# ina219.net
KiCad netlist of a schematic drawn in Altium Designer
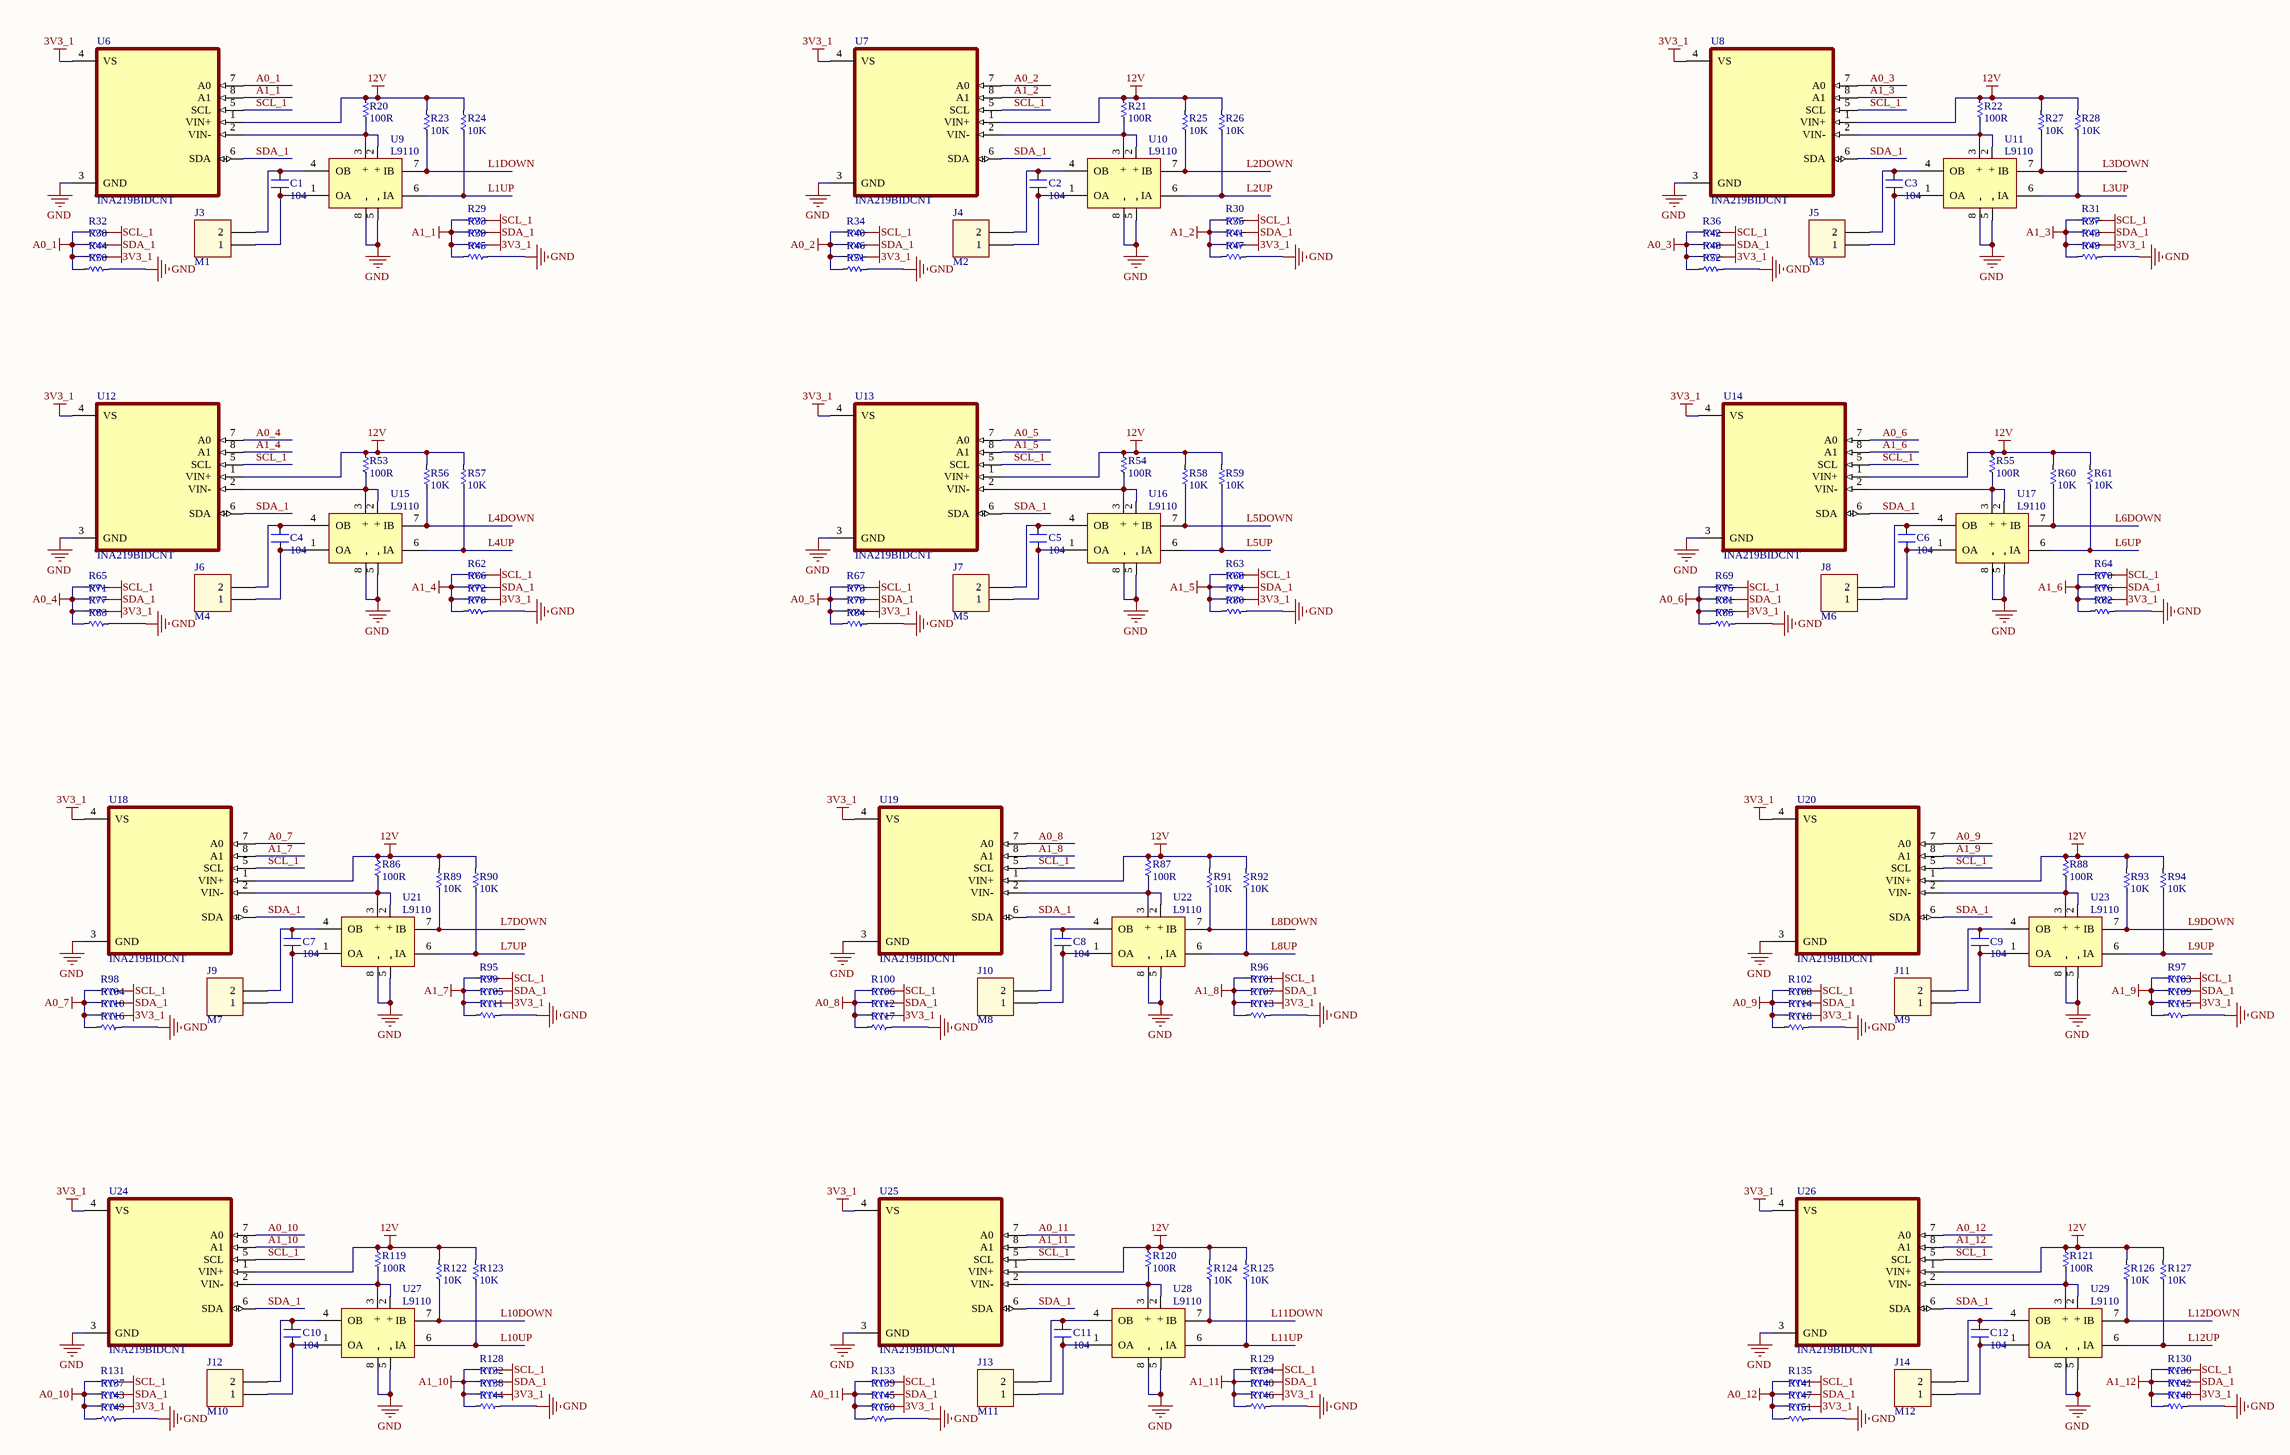
[diagram p0: ina219.SchDoc]

(export (version "E")
  (design (tool "Eeschema 10.0.6"))
  (components
    (comp (ref "C1")
      (value "104")
      (footprint "SM-CAP-0805")
      (fields (field (name "DESIGNED BY") "VanDungEvn"))
      (libsource (lib "electronicvn-library1") (part "CN"))
    )
    (comp (ref "C2")
      (value "104")
      (footprint "SM-CAP-0805")
      (fields (field (name "DESIGNED BY") "VanDungEvn"))
      (libsource (lib "electronicvn-library1") (part "CN"))
    )
    (comp (ref "C3")
      (value "104")
      (footprint "SM-CAP-0805")
      (fields (field (name "DESIGNED BY") "VanDungEvn"))
      (libsource (lib "electronicvn-library1") (part "CN"))
    )
    (comp (ref "C4")
      (value "104")
      (footprint "SM-CAP-0805")
      (fields (field (name "DESIGNED BY") "VanDungEvn"))
      (libsource (lib "electronicvn-library1") (part "CN"))
    )
    (comp (ref "C5")
      (value "104")
      (footprint "SM-CAP-0805")
      (fields (field (name "DESIGNED BY") "VanDungEvn"))
      (libsource (lib "electronicvn-library1") (part "CN"))
    )
    (comp (ref "C6")
      (value "104")
      (footprint "SM-CAP-0805")
      (fields (field (name "DESIGNED BY") "VanDungEvn"))
      (libsource (lib "electronicvn-library1") (part "CN"))
    )
    (comp (ref "C7")
      (value "104")
      (footprint "SM-CAP-0805")
      (fields (field (name "DESIGNED BY") "VanDungEvn"))
      (libsource (lib "electronicvn-library1") (part "CN"))
    )
    (comp (ref "C8")
      (value "104")
      (footprint "SM-CAP-0805")
      (fields (field (name "DESIGNED BY") "VanDungEvn"))
      (libsource (lib "electronicvn-library1") (part "CN"))
    )
    (comp (ref "C9")
      (value "104")
      (footprint "SM-CAP-0805")
      (fields (field (name "DESIGNED BY") "VanDungEvn"))
      (libsource (lib "electronicvn-library1") (part "CN"))
    )
    (comp (ref "C10")
      (value "104")
      (footprint "SM-CAP-0805")
      (fields (field (name "DESIGNED BY") "VanDungEvn"))
      (libsource (lib "electronicvn-library1") (part "CN"))
    )
    (comp (ref "C11")
      (value "104")
      (footprint "SM-CAP-0805")
      (fields (field (name "DESIGNED BY") "VanDungEvn"))
      (libsource (lib "electronicvn-library1") (part "CN"))
    )
    (comp (ref "C12")
      (value "104")
      (footprint "SM-CAP-0805")
      (fields (field (name "DESIGNED BY") "VanDungEvn"))
      (libsource (lib "electronicvn-library1") (part "CN"))
    )
    (comp (ref "J3")
      (value "M1")
      (footprint "62000211622")
      (description "WR-WTB 2.00mm Male Vertical Shrouded Header, 2p")
      (fields (field (name "PART NUMBER") "62000211622") (field (name "PUBLISHER") "Wurth Elektronik"))
      (libsource (lib "Header2.0") (part "62000211622"))
    )
    (comp (ref "J4")
      (value "M2")
      (footprint "62000211622")
      (description "WR-WTB 2.00mm Male Vertical Shrouded Header, 2p")
      (fields (field (name "PART NUMBER") "62000211622") (field (name "PUBLISHER") "Wurth Elektronik"))
      (libsource (lib "Header2.0") (part "62000211622"))
    )
    (comp (ref "J5")
      (value "M3")
      (footprint "62000211622")
      (description "WR-WTB 2.00mm Male Vertical Shrouded Header, 2p")
      (fields (field (name "PART NUMBER") "62000211622") (field (name "PUBLISHER") "Wurth Elektronik"))
      (libsource (lib "Header2.0") (part "62000211622"))
    )
    (comp (ref "J6")
      (value "M4")
      (footprint "62000211622")
      (description "WR-WTB 2.00mm Male Vertical Shrouded Header, 2p")
      (fields (field (name "PART NUMBER") "62000211622") (field (name "PUBLISHER") "Wurth Elektronik"))
      (libsource (lib "Header2.0") (part "62000211622"))
    )
    (comp (ref "J7")
      (value "M5")
      (footprint "62000211622")
      (description "WR-WTB 2.00mm Male Vertical Shrouded Header, 2p")
      (fields (field (name "PART NUMBER") "62000211622") (field (name "PUBLISHER") "Wurth Elektronik"))
      (libsource (lib "Header2.0") (part "62000211622"))
    )
    (comp (ref "J8")
      (value "M6")
      (footprint "62000211622")
      (description "WR-WTB 2.00mm Male Vertical Shrouded Header, 2p")
      (fields (field (name "PART NUMBER") "62000211622") (field (name "PUBLISHER") "Wurth Elektronik"))
      (libsource (lib "Header2.0") (part "62000211622"))
    )
    (comp (ref "J9")
      (value "M7")
      (footprint "62000211622")
      (description "WR-WTB 2.00mm Male Vertical Shrouded Header, 2p")
      (fields (field (name "PART NUMBER") "62000211622") (field (name "PUBLISHER") "Wurth Elektronik"))
      (libsource (lib "Header2.0") (part "62000211622"))
    )
    (comp (ref "J10")
      (value "M8")
      (footprint "62000211622")
      (description "WR-WTB 2.00mm Male Vertical Shrouded Header, 2p")
      (fields (field (name "PART NUMBER") "62000211622") (field (name "PUBLISHER") "Wurth Elektronik"))
      (libsource (lib "Header2.0") (part "62000211622"))
    )
    (comp (ref "J11")
      (value "M9")
      (footprint "62000211622")
      (description "WR-WTB 2.00mm Male Vertical Shrouded Header, 2p")
      (fields (field (name "PART NUMBER") "62000211622") (field (name "PUBLISHER") "Wurth Elektronik"))
      (libsource (lib "Header2.0") (part "62000211622"))
    )
    (comp (ref "J12")
      (value "M10")
      (footprint "62000211622")
      (description "WR-WTB 2.00mm Male Vertical Shrouded Header, 2p")
      (fields (field (name "PART NUMBER") "62000211622") (field (name "PUBLISHER") "Wurth Elektronik"))
      (libsource (lib "Header2.0") (part "62000211622"))
    )
    (comp (ref "J13")
      (value "M11")
      (footprint "62000211622")
      (description "WR-WTB 2.00mm Male Vertical Shrouded Header, 2p")
      (fields (field (name "PART NUMBER") "62000211622") (field (name "PUBLISHER") "Wurth Elektronik"))
      (libsource (lib "Header2.0") (part "62000211622"))
    )
    (comp (ref "J14")
      (value "M12")
      (footprint "62000211622")
      (description "WR-WTB 2.00mm Male Vertical Shrouded Header, 2p")
      (fields (field (name "PART NUMBER") "62000211622") (field (name "PUBLISHER") "Wurth Elektronik"))
      (libsource (lib "Header2.0") (part "62000211622"))
    )
    (comp (ref "R20")
      (value "100R")
      (footprint "RES-SMD-2512")
      (description "Resistor")
      (fields
        (field (name "MANUFACTURER") "Generic Components")
        (field (name "PUBLISHER") "Altium Hobart Technology Centre")
      )
      (libsource (lib "LIBRARY") (part "Res-SMD"))
    )
    (comp (ref "R21")
      (value "100R")
      (footprint "RES-SMD-2512")
      (description "Resistor")
      (fields
        (field (name "MANUFACTURER") "Generic Components")
        (field (name "PUBLISHER") "Altium Hobart Technology Centre")
      )
      (libsource (lib "LIBRARY") (part "Res-SMD"))
    )
    (comp (ref "R22")
      (value "100R")
      (footprint "RES-SMD-2512")
      (description "Resistor")
      (fields
        (field (name "MANUFACTURER") "Generic Components")
        (field (name "PUBLISHER") "Altium Hobart Technology Centre")
      )
      (libsource (lib "LIBRARY") (part "Res-SMD"))
    )
    (comp (ref "R23")
      (value "10K")
      (footprint "RES-SMD-0805")
      (description "Resistor")
      (fields
        (field (name "MANUFACTURER") "Generic Components")
        (field (name "PUBLISHER") "Altium Hobart Technology Centre")
      )
      (libsource (lib "LIBRARY") (part "Res-SMD"))
    )
    (comp (ref "R24")
      (value "10K")
      (footprint "RES-SMD-0805")
      (description "Resistor")
      (fields
        (field (name "MANUFACTURER") "Generic Components")
        (field (name "PUBLISHER") "Altium Hobart Technology Centre")
      )
      (libsource (lib "LIBRARY") (part "Res-SMD"))
    )
    (comp (ref "R25")
      (value "10K")
      (footprint "RES-SMD-0805")
      (description "Resistor")
      (fields
        (field (name "MANUFACTURER") "Generic Components")
        (field (name "PUBLISHER") "Altium Hobart Technology Centre")
      )
      (libsource (lib "LIBRARY") (part "Res-SMD"))
    )
    (comp (ref "R26")
      (value "10K")
      (footprint "RES-SMD-0805")
      (description "Resistor")
      (fields
        (field (name "MANUFACTURER") "Generic Components")
        (field (name "PUBLISHER") "Altium Hobart Technology Centre")
      )
      (libsource (lib "LIBRARY") (part "Res-SMD"))
    )
    (comp (ref "R27")
      (value "10K")
      (footprint "RES-SMD-0805")
      (description "Resistor")
      (fields
        (field (name "MANUFACTURER") "Generic Components")
        (field (name "PUBLISHER") "Altium Hobart Technology Centre")
      )
      (libsource (lib "LIBRARY") (part "Res-SMD"))
    )
    (comp (ref "R28")
      (value "10K")
      (footprint "RES-SMD-0805")
      (description "Resistor")
      (fields
        (field (name "MANUFACTURER") "Generic Components")
        (field (name "PUBLISHER") "Altium Hobart Technology Centre")
      )
      (libsource (lib "LIBRARY") (part "Res-SMD"))
    )
    (comp (ref "R29")
      (value "Res")
      (footprint "RES-SMD-0603")
      (description "Resistor")
      (fields
        (field (name "MANUFACTURER") "Generic Components")
        (field (name "PUBLISHER") "Altium Hobart Technology Centre")
      )
      (libsource (lib "LIBRARY") (part "Res-SMD"))
    )
    (comp (ref "R30")
      (value "Res")
      (footprint "RES-SMD-0603")
      (description "Resistor")
      (fields
        (field (name "MANUFACTURER") "Generic Components")
        (field (name "PUBLISHER") "Altium Hobart Technology Centre")
      )
      (libsource (lib "LIBRARY") (part "Res-SMD"))
    )
    (comp (ref "R31")
      (value "Res")
      (footprint "RES-SMD-0603")
      (description "Resistor")
      (fields
        (field (name "MANUFACTURER") "Generic Components")
        (field (name "PUBLISHER") "Altium Hobart Technology Centre")
      )
      (libsource (lib "LIBRARY") (part "Res-SMD"))
    )
    (comp (ref "R32")
      (value "Res")
      (footprint "RES-SMD-0603")
      (description "Resistor")
      (fields
        (field (name "MANUFACTURER") "Generic Components")
        (field (name "PUBLISHER") "Altium Hobart Technology Centre")
      )
      (libsource (lib "LIBRARY") (part "Res-SMD"))
    )
    (comp (ref "R33")
      (value "Res")
      (footprint "RES-SMD-0603")
      (description "Resistor")
      (fields
        (field (name "MANUFACTURER") "Generic Components")
        (field (name "PUBLISHER") "Altium Hobart Technology Centre")
      )
      (libsource (lib "LIBRARY") (part "Res-SMD"))
    )
    (comp (ref "R34")
      (value "Res")
      (footprint "RES-SMD-0603")
      (description "Resistor")
      (fields
        (field (name "MANUFACTURER") "Generic Components")
        (field (name "PUBLISHER") "Altium Hobart Technology Centre")
      )
      (libsource (lib "LIBRARY") (part "Res-SMD"))
    )
    (comp (ref "R35")
      (value "Res")
      (footprint "RES-SMD-0603")
      (description "Resistor")
      (fields
        (field (name "MANUFACTURER") "Generic Components")
        (field (name "PUBLISHER") "Altium Hobart Technology Centre")
      )
      (libsource (lib "LIBRARY") (part "Res-SMD"))
    )
    (comp (ref "R36")
      (value "Res")
      (footprint "RES-SMD-0603")
      (description "Resistor")
      (fields
        (field (name "MANUFACTURER") "Generic Components")
        (field (name "PUBLISHER") "Altium Hobart Technology Centre")
      )
      (libsource (lib "LIBRARY") (part "Res-SMD"))
    )
    (comp (ref "R37")
      (value "Res")
      (footprint "RES-SMD-0603")
      (description "Resistor")
      (fields
        (field (name "MANUFACTURER") "Generic Components")
        (field (name "PUBLISHER") "Altium Hobart Technology Centre")
      )
      (libsource (lib "LIBRARY") (part "Res-SMD"))
    )
    (comp (ref "R38")
      (value "Res")
      (footprint "RES-SMD-0603")
      (description "Resistor")
      (fields
        (field (name "MANUFACTURER") "Generic Components")
        (field (name "PUBLISHER") "Altium Hobart Technology Centre")
      )
      (libsource (lib "LIBRARY") (part "Res-SMD"))
    )
    (comp (ref "R39")
      (value "Res")
      (footprint "RES-SMD-0603")
      (description "Resistor")
      (fields
        (field (name "MANUFACTURER") "Generic Components")
        (field (name "PUBLISHER") "Altium Hobart Technology Centre")
      )
      (libsource (lib "LIBRARY") (part "Res-SMD"))
    )
    (comp (ref "R40")
      (value "Res")
      (footprint "RES-SMD-0603")
      (description "Resistor")
      (fields
        (field (name "MANUFACTURER") "Generic Components")
        (field (name "PUBLISHER") "Altium Hobart Technology Centre")
      )
      (libsource (lib "LIBRARY") (part "Res-SMD"))
    )
    (comp (ref "R41")
      (value "Res")
      (footprint "RES-SMD-0603")
      (description "Resistor")
      (fields
        (field (name "MANUFACTURER") "Generic Components")
        (field (name "PUBLISHER") "Altium Hobart Technology Centre")
      )
      (libsource (lib "LIBRARY") (part "Res-SMD"))
    )
    (comp (ref "R42")
      (value "Res")
      (footprint "RES-SMD-0603")
      (description "Resistor")
      (fields
        (field (name "MANUFACTURER") "Generic Components")
        (field (name "PUBLISHER") "Altium Hobart Technology Centre")
      )
      (libsource (lib "LIBRARY") (part "Res-SMD"))
    )
    (comp (ref "R43")
      (value "Res")
      (footprint "RES-SMD-0603")
      (description "Resistor")
      (fields
        (field (name "MANUFACTURER") "Generic Components")
        (field (name "PUBLISHER") "Altium Hobart Technology Centre")
      )
      (libsource (lib "LIBRARY") (part "Res-SMD"))
    )
    (comp (ref "R44")
      (value "Res")
      (footprint "RES-SMD-0603")
      (description "Resistor")
      (fields
        (field (name "MANUFACTURER") "Generic Components")
        (field (name "PUBLISHER") "Altium Hobart Technology Centre")
      )
      (libsource (lib "LIBRARY") (part "Res-SMD"))
    )
    (comp (ref "R45")
      (value "Res")
      (footprint "RES-SMD-0603")
      (description "Resistor")
      (fields
        (field (name "MANUFACTURER") "Generic Components")
        (field (name "PUBLISHER") "Altium Hobart Technology Centre")
      )
      (libsource (lib "LIBRARY") (part "Res-SMD"))
    )
    (comp (ref "R46")
      (value "Res")
      (footprint "RES-SMD-0603")
      (description "Resistor")
      (fields
        (field (name "MANUFACTURER") "Generic Components")
        (field (name "PUBLISHER") "Altium Hobart Technology Centre")
      )
      (libsource (lib "LIBRARY") (part "Res-SMD"))
    )
    (comp (ref "R47")
      (value "Res")
      (footprint "RES-SMD-0603")
      (description "Resistor")
      (fields
        (field (name "MANUFACTURER") "Generic Components")
        (field (name "PUBLISHER") "Altium Hobart Technology Centre")
      )
      (libsource (lib "LIBRARY") (part "Res-SMD"))
    )
    (comp (ref "R48")
      (value "Res")
      (footprint "RES-SMD-0603")
      (description "Resistor")
      (fields
        (field (name "MANUFACTURER") "Generic Components")
        (field (name "PUBLISHER") "Altium Hobart Technology Centre")
      )
      (libsource (lib "LIBRARY") (part "Res-SMD"))
    )
    (comp (ref "R49")
      (value "Res")
      (footprint "RES-SMD-0603")
      (description "Resistor")
      (fields
        (field (name "MANUFACTURER") "Generic Components")
        (field (name "PUBLISHER") "Altium Hobart Technology Centre")
      )
      (libsource (lib "LIBRARY") (part "Res-SMD"))
    )
    (comp (ref "R50")
      (value "Res")
      (footprint "RES-SMD-0603")
      (description "Resistor")
      (fields
        (field (name "MANUFACTURER") "Generic Components")
        (field (name "PUBLISHER") "Altium Hobart Technology Centre")
      )
      (libsource (lib "LIBRARY") (part "Res-SMD"))
    )
    (comp (ref "R51")
      (value "Res")
      (footprint "RES-SMD-0603")
      (description "Resistor")
      (fields
        (field (name "MANUFACTURER") "Generic Components")
        (field (name "PUBLISHER") "Altium Hobart Technology Centre")
      )
      (libsource (lib "LIBRARY") (part "Res-SMD"))
    )
    (comp (ref "R52")
      (value "Res")
      (footprint "RES-SMD-0603")
      (description "Resistor")
      (fields
        (field (name "MANUFACTURER") "Generic Components")
        (field (name "PUBLISHER") "Altium Hobart Technology Centre")
      )
      (libsource (lib "LIBRARY") (part "Res-SMD"))
    )
    (comp (ref "R53")
      (value "100R")
      (footprint "RES-SMD-2512")
      (description "Resistor")
      (fields
        (field (name "MANUFACTURER") "Generic Components")
        (field (name "PUBLISHER") "Altium Hobart Technology Centre")
      )
      (libsource (lib "LIBRARY") (part "Res-SMD"))
    )
    (comp (ref "R54")
      (value "100R")
      (footprint "RES-SMD-2512")
      (description "Resistor")
      (fields
        (field (name "MANUFACTURER") "Generic Components")
        (field (name "PUBLISHER") "Altium Hobart Technology Centre")
      )
      (libsource (lib "LIBRARY") (part "Res-SMD"))
    )
    (comp (ref "R55")
      (value "100R")
      (footprint "RES-SMD-2512")
      (description "Resistor")
      (fields
        (field (name "MANUFACTURER") "Generic Components")
        (field (name "PUBLISHER") "Altium Hobart Technology Centre")
      )
      (libsource (lib "LIBRARY") (part "Res-SMD"))
    )
    (comp (ref "R56")
      (value "10K")
      (footprint "RES-SMD-0805")
      (description "Resistor")
      (fields
        (field (name "MANUFACTURER") "Generic Components")
        (field (name "PUBLISHER") "Altium Hobart Technology Centre")
      )
      (libsource (lib "LIBRARY") (part "Res-SMD"))
    )
    (comp (ref "R57")
      (value "10K")
      (footprint "RES-SMD-0805")
      (description "Resistor")
      (fields
        (field (name "MANUFACTURER") "Generic Components")
        (field (name "PUBLISHER") "Altium Hobart Technology Centre")
      )
      (libsource (lib "LIBRARY") (part "Res-SMD"))
    )
    (comp (ref "R58")
      (value "10K")
      (footprint "RES-SMD-0805")
      (description "Resistor")
      (fields
        (field (name "MANUFACTURER") "Generic Components")
        (field (name "PUBLISHER") "Altium Hobart Technology Centre")
      )
      (libsource (lib "LIBRARY") (part "Res-SMD"))
    )
    (comp (ref "R59")
      (value "10K")
      (footprint "RES-SMD-0805")
      (description "Resistor")
      (fields
        (field (name "MANUFACTURER") "Generic Components")
        (field (name "PUBLISHER") "Altium Hobart Technology Centre")
      )
      (libsource (lib "LIBRARY") (part "Res-SMD"))
    )
    (comp (ref "R60")
      (value "10K")
      (footprint "RES-SMD-0805")
      (description "Resistor")
      (fields
        (field (name "MANUFACTURER") "Generic Components")
        (field (name "PUBLISHER") "Altium Hobart Technology Centre")
      )
      (libsource (lib "LIBRARY") (part "Res-SMD"))
    )
    (comp (ref "R61")
      (value "10K")
      (footprint "RES-SMD-0805")
      (description "Resistor")
      (fields
        (field (name "MANUFACTURER") "Generic Components")
        (field (name "PUBLISHER") "Altium Hobart Technology Centre")
      )
      (libsource (lib "LIBRARY") (part "Res-SMD"))
    )
    (comp (ref "R62")
      (value "Res")
      (footprint "RES-SMD-0603")
      (description "Resistor")
      (fields
        (field (name "MANUFACTURER") "Generic Components")
        (field (name "PUBLISHER") "Altium Hobart Technology Centre")
      )
      (libsource (lib "LIBRARY") (part "Res-SMD"))
    )
    (comp (ref "R63")
      (value "Res")
      (footprint "RES-SMD-0603")
      (description "Resistor")
      (fields
        (field (name "MANUFACTURER") "Generic Components")
        (field (name "PUBLISHER") "Altium Hobart Technology Centre")
      )
      (libsource (lib "LIBRARY") (part "Res-SMD"))
    )
    (comp (ref "R64")
      (value "Res")
      (footprint "RES-SMD-0603")
      (description "Resistor")
      (fields
        (field (name "MANUFACTURER") "Generic Components")
        (field (name "PUBLISHER") "Altium Hobart Technology Centre")
      )
      (libsource (lib "LIBRARY") (part "Res-SMD"))
    )
    (comp (ref "R65")
      (value "Res")
      (footprint "RES-SMD-0603")
      (description "Resistor")
      (fields
        (field (name "MANUFACTURER") "Generic Components")
        (field (name "PUBLISHER") "Altium Hobart Technology Centre")
      )
      (libsource (lib "LIBRARY") (part "Res-SMD"))
    )
    (comp (ref "R66")
      (value "Res")
      (footprint "RES-SMD-0603")
      (description "Resistor")
      (fields
        (field (name "MANUFACTURER") "Generic Components")
        (field (name "PUBLISHER") "Altium Hobart Technology Centre")
      )
      (libsource (lib "LIBRARY") (part "Res-SMD"))
    )
    (comp (ref "R67")
      (value "Res")
      (footprint "RES-SMD-0603")
      (description "Resistor")
      (fields
        (field (name "MANUFACTURER") "Generic Components")
        (field (name "PUBLISHER") "Altium Hobart Technology Centre")
      )
      (libsource (lib "LIBRARY") (part "Res-SMD"))
    )
    (comp (ref "R68")
      (value "Res")
      (footprint "RES-SMD-0603")
      (description "Resistor")
      (fields
        (field (name "MANUFACTURER") "Generic Components")
        (field (name "PUBLISHER") "Altium Hobart Technology Centre")
      )
      (libsource (lib "LIBRARY") (part "Res-SMD"))
    )
    (comp (ref "R69")
      (value "Res")
      (footprint "RES-SMD-0603")
      (description "Resistor")
      (fields
        (field (name "MANUFACTURER") "Generic Components")
        (field (name "PUBLISHER") "Altium Hobart Technology Centre")
      )
      (libsource (lib "LIBRARY") (part "Res-SMD"))
    )
    (comp (ref "R70")
      (value "Res")
      (footprint "RES-SMD-0603")
      (description "Resistor")
      (fields
        (field (name "MANUFACTURER") "Generic Components")
        (field (name "PUBLISHER") "Altium Hobart Technology Centre")
      )
      (libsource (lib "LIBRARY") (part "Res-SMD"))
    )
    (comp (ref "R71")
      (value "Res")
      (footprint "RES-SMD-0603")
      (description "Resistor")
      (fields
        (field (name "MANUFACTURER") "Generic Components")
        (field (name "PUBLISHER") "Altium Hobart Technology Centre")
      )
      (libsource (lib "LIBRARY") (part "Res-SMD"))
    )
    (comp (ref "R72")
      (value "Res")
      (footprint "RES-SMD-0603")
      (description "Resistor")
      (fields
        (field (name "MANUFACTURER") "Generic Components")
        (field (name "PUBLISHER") "Altium Hobart Technology Centre")
      )
      (libsource (lib "LIBRARY") (part "Res-SMD"))
    )
    (comp (ref "R73")
      (value "Res")
      (footprint "RES-SMD-0603")
      (description "Resistor")
      (fields
        (field (name "MANUFACTURER") "Generic Components")
        (field (name "PUBLISHER") "Altium Hobart Technology Centre")
      )
      (libsource (lib "LIBRARY") (part "Res-SMD"))
    )
    (comp (ref "R74")
      (value "Res")
      (footprint "RES-SMD-0603")
      (description "Resistor")
      (fields
        (field (name "MANUFACTURER") "Generic Components")
        (field (name "PUBLISHER") "Altium Hobart Technology Centre")
      )
      (libsource (lib "LIBRARY") (part "Res-SMD"))
    )
    (comp (ref "R75")
      (value "Res")
      (footprint "RES-SMD-0603")
      (description "Resistor")
      (fields
        (field (name "MANUFACTURER") "Generic Components")
        (field (name "PUBLISHER") "Altium Hobart Technology Centre")
      )
      (libsource (lib "LIBRARY") (part "Res-SMD"))
    )
    (comp (ref "R76")
      (value "Res")
      (footprint "RES-SMD-0603")
      (description "Resistor")
      (fields
        (field (name "MANUFACTURER") "Generic Components")
        (field (name "PUBLISHER") "Altium Hobart Technology Centre")
      )
      (libsource (lib "LIBRARY") (part "Res-SMD"))
    )
    (comp (ref "R77")
      (value "Res")
      (footprint "RES-SMD-0603")
      (description "Resistor")
      (fields
        (field (name "MANUFACTURER") "Generic Components")
        (field (name "PUBLISHER") "Altium Hobart Technology Centre")
      )
      (libsource (lib "LIBRARY") (part "Res-SMD"))
    )
    (comp (ref "R78")
      (value "Res")
      (footprint "RES-SMD-0603")
      (description "Resistor")
      (fields
        (field (name "MANUFACTURER") "Generic Components")
        (field (name "PUBLISHER") "Altium Hobart Technology Centre")
      )
      (libsource (lib "LIBRARY") (part "Res-SMD"))
    )
    (comp (ref "R79")
      (value "Res")
      (footprint "RES-SMD-0603")
      (description "Resistor")
      (fields
        (field (name "MANUFACTURER") "Generic Components")
        (field (name "PUBLISHER") "Altium Hobart Technology Centre")
      )
      (libsource (lib "LIBRARY") (part "Res-SMD"))
    )
    (comp (ref "R80")
      (value "Res")
      (footprint "RES-SMD-0603")
      (description "Resistor")
      (fields
        (field (name "MANUFACTURER") "Generic Components")
        (field (name "PUBLISHER") "Altium Hobart Technology Centre")
      )
      (libsource (lib "LIBRARY") (part "Res-SMD"))
    )
    (comp (ref "R81")
      (value "Res")
      (footprint "RES-SMD-0603")
      (description "Resistor")
      (fields
        (field (name "MANUFACTURER") "Generic Components")
        (field (name "PUBLISHER") "Altium Hobart Technology Centre")
      )
      (libsource (lib "LIBRARY") (part "Res-SMD"))
    )
    (comp (ref "R82")
      (value "Res")
      (footprint "RES-SMD-0603")
      (description "Resistor")
      (fields
        (field (name "MANUFACTURER") "Generic Components")
        (field (name "PUBLISHER") "Altium Hobart Technology Centre")
      )
      (libsource (lib "LIBRARY") (part "Res-SMD"))
    )
    (comp (ref "R83")
      (value "Res")
      (footprint "RES-SMD-0603")
      (description "Resistor")
      (fields
        (field (name "MANUFACTURER") "Generic Components")
        (field (name "PUBLISHER") "Altium Hobart Technology Centre")
      )
      (libsource (lib "LIBRARY") (part "Res-SMD"))
    )
    (comp (ref "R84")
      (value "Res")
      (footprint "RES-SMD-0603")
      (description "Resistor")
      (fields
        (field (name "MANUFACTURER") "Generic Components")
        (field (name "PUBLISHER") "Altium Hobart Technology Centre")
      )
      (libsource (lib "LIBRARY") (part "Res-SMD"))
    )
    (comp (ref "R85")
      (value "Res")
      (footprint "RES-SMD-0603")
      (description "Resistor")
      (fields
        (field (name "MANUFACTURER") "Generic Components")
        (field (name "PUBLISHER") "Altium Hobart Technology Centre")
      )
      (libsource (lib "LIBRARY") (part "Res-SMD"))
    )
    (comp (ref "R86")
      (value "100R")
      (footprint "RES-SMD-2512")
      (description "Resistor")
      (fields
        (field (name "MANUFACTURER") "Generic Components")
        (field (name "PUBLISHER") "Altium Hobart Technology Centre")
      )
      (libsource (lib "LIBRARY") (part "Res-SMD"))
    )
    (comp (ref "R87")
      (value "100R")
      (footprint "RES-SMD-2512")
      (description "Resistor")
      (fields
        (field (name "MANUFACTURER") "Generic Components")
        (field (name "PUBLISHER") "Altium Hobart Technology Centre")
      )
      (libsource (lib "LIBRARY") (part "Res-SMD"))
    )
    (comp (ref "R88")
      (value "100R")
      (footprint "RES-SMD-2512")
      (description "Resistor")
      (fields
        (field (name "MANUFACTURER") "Generic Components")
        (field (name "PUBLISHER") "Altium Hobart Technology Centre")
      )
      (libsource (lib "LIBRARY") (part "Res-SMD"))
    )
    (comp (ref "R89")
      (value "10K")
      (footprint "RES-SMD-0805")
      (description "Resistor")
      (fields
        (field (name "MANUFACTURER") "Generic Components")
        (field (name "PUBLISHER") "Altium Hobart Technology Centre")
      )
      (libsource (lib "LIBRARY") (part "Res-SMD"))
    )
    (comp (ref "R90")
      (value "10K")
      (footprint "RES-SMD-0805")
      (description "Resistor")
      (fields
        (field (name "MANUFACTURER") "Generic Components")
        (field (name "PUBLISHER") "Altium Hobart Technology Centre")
      )
      (libsource (lib "LIBRARY") (part "Res-SMD"))
    )
    (comp (ref "R91")
      (value "10K")
      (footprint "RES-SMD-0805")
      (description "Resistor")
      (fields
        (field (name "MANUFACTURER") "Generic Components")
        (field (name "PUBLISHER") "Altium Hobart Technology Centre")
      )
      (libsource (lib "LIBRARY") (part "Res-SMD"))
    )
    (comp (ref "R92")
      (value "10K")
      (footprint "RES-SMD-0805")
      (description "Resistor")
      (fields
        (field (name "MANUFACTURER") "Generic Components")
        (field (name "PUBLISHER") "Altium Hobart Technology Centre")
      )
      (libsource (lib "LIBRARY") (part "Res-SMD"))
    )
    (comp (ref "R93")
      (value "10K")
      (footprint "RES-SMD-0805")
      (description "Resistor")
      (fields
        (field (name "MANUFACTURER") "Generic Components")
        (field (name "PUBLISHER") "Altium Hobart Technology Centre")
      )
      (libsource (lib "LIBRARY") (part "Res-SMD"))
    )
    (comp (ref "R94")
      (value "10K")
      (footprint "RES-SMD-0805")
      (description "Resistor")
      (fields
        (field (name "MANUFACTURER") "Generic Components")
        (field (name "PUBLISHER") "Altium Hobart Technology Centre")
      )
      (libsource (lib "LIBRARY") (part "Res-SMD"))
    )
    (comp (ref "R95")
      (value "Res")
      (footprint "RES-SMD-0603")
      (description "Resistor")
      (fields
        (field (name "MANUFACTURER") "Generic Components")
        (field (name "PUBLISHER") "Altium Hobart Technology Centre")
      )
      (libsource (lib "LIBRARY") (part "Res-SMD"))
    )
    (comp (ref "R96")
      (value "Res")
      (footprint "RES-SMD-0603")
      (description "Resistor")
      (fields
        (field (name "MANUFACTURER") "Generic Components")
        (field (name "PUBLISHER") "Altium Hobart Technology Centre")
      )
      (libsource (lib "LIBRARY") (part "Res-SMD"))
    )
    (comp (ref "R97")
      (value "Res")
      (footprint "RES-SMD-0603")
      (description "Resistor")
      (fields
        (field (name "MANUFACTURER") "Generic Components")
        (field (name "PUBLISHER") "Altium Hobart Technology Centre")
      )
      (libsource (lib "LIBRARY") (part "Res-SMD"))
    )
    (comp (ref "R98")
      (value "Res")
      (footprint "RES-SMD-0603")
      (description "Resistor")
      (fields
        (field (name "MANUFACTURER") "Generic Components")
        (field (name "PUBLISHER") "Altium Hobart Technology Centre")
      )
      (libsource (lib "LIBRARY") (part "Res-SMD"))
    )
    (comp (ref "R99")
      (value "Res")
      (footprint "RES-SMD-0603")
      (description "Resistor")
      (fields
        (field (name "MANUFACTURER") "Generic Components")
        (field (name "PUBLISHER") "Altium Hobart Technology Centre")
      )
      (libsource (lib "LIBRARY") (part "Res-SMD"))
    )
    (comp (ref "R100")
      (value "Res")
      (footprint "RES-SMD-0603")
      (description "Resistor")
      (fields
        (field (name "MANUFACTURER") "Generic Components")
        (field (name "PUBLISHER") "Altium Hobart Technology Centre")
      )
      (libsource (lib "LIBRARY") (part "Res-SMD"))
    )
    (comp (ref "R101")
      (value "Res")
      (footprint "RES-SMD-0603")
      (description "Resistor")
      (fields
        (field (name "MANUFACTURER") "Generic Components")
        (field (name "PUBLISHER") "Altium Hobart Technology Centre")
      )
      (libsource (lib "LIBRARY") (part "Res-SMD"))
    )
    (comp (ref "R102")
      (value "Res")
      (footprint "RES-SMD-0603")
      (description "Resistor")
      (fields
        (field (name "MANUFACTURER") "Generic Components")
        (field (name "PUBLISHER") "Altium Hobart Technology Centre")
      )
      (libsource (lib "LIBRARY") (part "Res-SMD"))
    )
    (comp (ref "R103")
      (value "Res")
      (footprint "RES-SMD-0603")
      (description "Resistor")
      (fields
        (field (name "MANUFACTURER") "Generic Components")
        (field (name "PUBLISHER") "Altium Hobart Technology Centre")
      )
      (libsource (lib "LIBRARY") (part "Res-SMD"))
    )
    (comp (ref "R104")
      (value "Res")
      (footprint "RES-SMD-0603")
      (description "Resistor")
      (fields
        (field (name "MANUFACTURER") "Generic Components")
        (field (name "PUBLISHER") "Altium Hobart Technology Centre")
      )
      (libsource (lib "LIBRARY") (part "Res-SMD"))
    )
    (comp (ref "R105")
      (value "Res")
      (footprint "RES-SMD-0603")
      (description "Resistor")
      (fields
        (field (name "MANUFACTURER") "Generic Components")
        (field (name "PUBLISHER") "Altium Hobart Technology Centre")
      )
      (libsource (lib "LIBRARY") (part "Res-SMD"))
    )
    (comp (ref "R106")
      (value "Res")
      (footprint "RES-SMD-0603")
      (description "Resistor")
      (fields
        (field (name "MANUFACTURER") "Generic Components")
        (field (name "PUBLISHER") "Altium Hobart Technology Centre")
      )
      (libsource (lib "LIBRARY") (part "Res-SMD"))
    )
    (comp (ref "R107")
      (value "Res")
      (footprint "RES-SMD-0603")
      (description "Resistor")
      (fields
        (field (name "MANUFACTURER") "Generic Components")
        (field (name "PUBLISHER") "Altium Hobart Technology Centre")
      )
      (libsource (lib "LIBRARY") (part "Res-SMD"))
    )
    (comp (ref "R108")
      (value "Res")
      (footprint "RES-SMD-0603")
      (description "Resistor")
      (fields
        (field (name "MANUFACTURER") "Generic Components")
        (field (name "PUBLISHER") "Altium Hobart Technology Centre")
      )
      (libsource (lib "LIBRARY") (part "Res-SMD"))
    )
    (comp (ref "R109")
      (value "Res")
      (footprint "RES-SMD-0603")
      (description "Resistor")
      (fields
        (field (name "MANUFACTURER") "Generic Components")
        (field (name "PUBLISHER") "Altium Hobart Technology Centre")
      )
      (libsource (lib "LIBRARY") (part "Res-SMD"))
    )
    (comp (ref "R110")
      (value "Res")
      (footprint "RES-SMD-0603")
      (description "Resistor")
      (fields
        (field (name "MANUFACTURER") "Generic Components")
        (field (name "PUBLISHER") "Altium Hobart Technology Centre")
      )
      (libsource (lib "LIBRARY") (part "Res-SMD"))
    )
    (comp (ref "R111")
      (value "Res")
      (footprint "RES-SMD-0603")
      (description "Resistor")
      (fields
        (field (name "MANUFACTURER") "Generic Components")
        (field (name "PUBLISHER") "Altium Hobart Technology Centre")
      )
      (libsource (lib "LIBRARY") (part "Res-SMD"))
    )
    (comp (ref "R112")
      (value "Res")
      (footprint "RES-SMD-0603")
      (description "Resistor")
      (fields
        (field (name "MANUFACTURER") "Generic Components")
        (field (name "PUBLISHER") "Altium Hobart Technology Centre")
      )
      (libsource (lib "LIBRARY") (part "Res-SMD"))
    )
    (comp (ref "R113")
      (value "Res")
      (footprint "RES-SMD-0603")
      (description "Resistor")
      (fields
        (field (name "MANUFACTURER") "Generic Components")
        (field (name "PUBLISHER") "Altium Hobart Technology Centre")
      )
      (libsource (lib "LIBRARY") (part "Res-SMD"))
    )
    (comp (ref "R114")
      (value "Res")
      (footprint "RES-SMD-0603")
      (description "Resistor")
      (fields
        (field (name "MANUFACTURER") "Generic Components")
        (field (name "PUBLISHER") "Altium Hobart Technology Centre")
      )
      (libsource (lib "LIBRARY") (part "Res-SMD"))
    )
    (comp (ref "R115")
      (value "Res")
      (footprint "RES-SMD-0603")
      (description "Resistor")
      (fields
        (field (name "MANUFACTURER") "Generic Components")
        (field (name "PUBLISHER") "Altium Hobart Technology Centre")
      )
      (libsource (lib "LIBRARY") (part "Res-SMD"))
    )
    (comp (ref "R116")
      (value "Res")
      (footprint "RES-SMD-0603")
      (description "Resistor")
      (fields
        (field (name "MANUFACTURER") "Generic Components")
        (field (name "PUBLISHER") "Altium Hobart Technology Centre")
      )
      (libsource (lib "LIBRARY") (part "Res-SMD"))
    )
    (comp (ref "R117")
      (value "Res")
      (footprint "RES-SMD-0603")
      (description "Resistor")
      (fields
        (field (name "MANUFACTURER") "Generic Components")
        (field (name "PUBLISHER") "Altium Hobart Technology Centre")
      )
      (libsource (lib "LIBRARY") (part "Res-SMD"))
    )
    (comp (ref "R118")
      (value "Res")
      (footprint "RES-SMD-0603")
      (description "Resistor")
      (fields
        (field (name "MANUFACTURER") "Generic Components")
        (field (name "PUBLISHER") "Altium Hobart Technology Centre")
      )
      (libsource (lib "LIBRARY") (part "Res-SMD"))
    )
    (comp (ref "R119")
      (value "100R")
      (footprint "RES-SMD-2512")
      (description "Resistor")
      (fields
        (field (name "MANUFACTURER") "Generic Components")
        (field (name "PUBLISHER") "Altium Hobart Technology Centre")
      )
      (libsource (lib "LIBRARY") (part "Res-SMD"))
    )
    (comp (ref "R120")
      (value "100R")
      (footprint "RES-SMD-2512")
      (description "Resistor")
      (fields
        (field (name "MANUFACTURER") "Generic Components")
        (field (name "PUBLISHER") "Altium Hobart Technology Centre")
      )
      (libsource (lib "LIBRARY") (part "Res-SMD"))
    )
    (comp (ref "R121")
      (value "100R")
      (footprint "RES-SMD-2512")
      (description "Resistor")
      (fields
        (field (name "MANUFACTURER") "Generic Components")
        (field (name "PUBLISHER") "Altium Hobart Technology Centre")
      )
      (libsource (lib "LIBRARY") (part "Res-SMD"))
    )
    (comp (ref "R122")
      (value "10K")
      (footprint "RES-SMD-0805")
      (description "Resistor")
      (fields
        (field (name "MANUFACTURER") "Generic Components")
        (field (name "PUBLISHER") "Altium Hobart Technology Centre")
      )
      (libsource (lib "LIBRARY") (part "Res-SMD"))
    )
    (comp (ref "R123")
      (value "10K")
      (footprint "RES-SMD-0805")
      (description "Resistor")
      (fields
        (field (name "MANUFACTURER") "Generic Components")
        (field (name "PUBLISHER") "Altium Hobart Technology Centre")
      )
      (libsource (lib "LIBRARY") (part "Res-SMD"))
    )
    (comp (ref "R124")
      (value "10K")
      (footprint "RES-SMD-0805")
      (description "Resistor")
      (fields
        (field (name "MANUFACTURER") "Generic Components")
        (field (name "PUBLISHER") "Altium Hobart Technology Centre")
      )
      (libsource (lib "LIBRARY") (part "Res-SMD"))
    )
    (comp (ref "R125")
      (value "10K")
      (footprint "RES-SMD-0805")
      (description "Resistor")
      (fields
        (field (name "MANUFACTURER") "Generic Components")
        (field (name "PUBLISHER") "Altium Hobart Technology Centre")
      )
      (libsource (lib "LIBRARY") (part "Res-SMD"))
    )
    (comp (ref "R126")
      (value "10K")
      (footprint "RES-SMD-0805")
      (description "Resistor")
      (fields
        (field (name "MANUFACTURER") "Generic Components")
        (field (name "PUBLISHER") "Altium Hobart Technology Centre")
      )
      (libsource (lib "LIBRARY") (part "Res-SMD"))
    )
    (comp (ref "R127")
      (value "10K")
      (footprint "RES-SMD-0805")
      (description "Resistor")
      (fields
        (field (name "MANUFACTURER") "Generic Components")
        (field (name "PUBLISHER") "Altium Hobart Technology Centre")
      )
      (libsource (lib "LIBRARY") (part "Res-SMD"))
    )
    (comp (ref "R128")
      (value "Res")
      (footprint "RES-SMD-0603")
      (description "Resistor")
      (fields
        (field (name "MANUFACTURER") "Generic Components")
        (field (name "PUBLISHER") "Altium Hobart Technology Centre")
      )
      (libsource (lib "LIBRARY") (part "Res-SMD"))
    )
    (comp (ref "R129")
      (value "Res")
      (footprint "RES-SMD-0603")
      (description "Resistor")
      (fields
        (field (name "MANUFACTURER") "Generic Components")
        (field (name "PUBLISHER") "Altium Hobart Technology Centre")
      )
      (libsource (lib "LIBRARY") (part "Res-SMD"))
    )
    (comp (ref "R130")
      (value "Res")
      (footprint "RES-SMD-0603")
      (description "Resistor")
      (fields
        (field (name "MANUFACTURER") "Generic Components")
        (field (name "PUBLISHER") "Altium Hobart Technology Centre")
      )
      (libsource (lib "LIBRARY") (part "Res-SMD"))
    )
    (comp (ref "R131")
      (value "Res")
      (footprint "RES-SMD-0603")
      (description "Resistor")
      (fields
        (field (name "MANUFACTURER") "Generic Components")
        (field (name "PUBLISHER") "Altium Hobart Technology Centre")
      )
      (libsource (lib "LIBRARY") (part "Res-SMD"))
    )
    (comp (ref "R132")
      (value "Res")
      (footprint "RES-SMD-0603")
      (description "Resistor")
      (fields
        (field (name "MANUFACTURER") "Generic Components")
        (field (name "PUBLISHER") "Altium Hobart Technology Centre")
      )
      (libsource (lib "LIBRARY") (part "Res-SMD"))
    )
    (comp (ref "R133")
      (value "Res")
      (footprint "RES-SMD-0603")
      (description "Resistor")
      (fields
        (field (name "MANUFACTURER") "Generic Components")
        (field (name "PUBLISHER") "Altium Hobart Technology Centre")
      )
      (libsource (lib "LIBRARY") (part "Res-SMD"))
    )
    (comp (ref "R134")
      (value "Res")
      (footprint "RES-SMD-0603")
      (description "Resistor")
      (fields
        (field (name "MANUFACTURER") "Generic Components")
        (field (name "PUBLISHER") "Altium Hobart Technology Centre")
      )
      (libsource (lib "LIBRARY") (part "Res-SMD"))
    )
    (comp (ref "R135")
      (value "Res")
      (footprint "RES-SMD-0603")
      (description "Resistor")
      (fields
        (field (name "MANUFACTURER") "Generic Components")
        (field (name "PUBLISHER") "Altium Hobart Technology Centre")
      )
      (libsource (lib "LIBRARY") (part "Res-SMD"))
    )
    (comp (ref "R136")
      (value "Res")
      (footprint "RES-SMD-0603")
      (description "Resistor")
      (fields
        (field (name "MANUFACTURER") "Generic Components")
        (field (name "PUBLISHER") "Altium Hobart Technology Centre")
      )
      (libsource (lib "LIBRARY") (part "Res-SMD"))
    )
    (comp (ref "R137")
      (value "Res")
      (footprint "RES-SMD-0603")
      (description "Resistor")
      (fields
        (field (name "MANUFACTURER") "Generic Components")
        (field (name "PUBLISHER") "Altium Hobart Technology Centre")
      )
      (libsource (lib "LIBRARY") (part "Res-SMD"))
    )
    (comp (ref "R138")
      (value "Res")
      (footprint "RES-SMD-0603")
      (description "Resistor")
      (fields
        (field (name "MANUFACTURER") "Generic Components")
        (field (name "PUBLISHER") "Altium Hobart Technology Centre")
      )
      (libsource (lib "LIBRARY") (part "Res-SMD"))
    )
    (comp (ref "R139")
      (value "Res")
      (footprint "RES-SMD-0603")
      (description "Resistor")
      (fields
        (field (name "MANUFACTURER") "Generic Components")
        (field (name "PUBLISHER") "Altium Hobart Technology Centre")
      )
      (libsource (lib "LIBRARY") (part "Res-SMD"))
    )
    (comp (ref "R140")
      (value "Res")
      (footprint "RES-SMD-0603")
      (description "Resistor")
      (fields
        (field (name "MANUFACTURER") "Generic Components")
        (field (name "PUBLISHER") "Altium Hobart Technology Centre")
      )
      (libsource (lib "LIBRARY") (part "Res-SMD"))
    )
    (comp (ref "R141")
      (value "Res")
      (footprint "RES-SMD-0603")
      (description "Resistor")
      (fields
        (field (name "MANUFACTURER") "Generic Components")
        (field (name "PUBLISHER") "Altium Hobart Technology Centre")
      )
      (libsource (lib "LIBRARY") (part "Res-SMD"))
    )
    (comp (ref "R142")
      (value "Res")
      (footprint "RES-SMD-0603")
      (description "Resistor")
      (fields
        (field (name "MANUFACTURER") "Generic Components")
        (field (name "PUBLISHER") "Altium Hobart Technology Centre")
      )
      (libsource (lib "LIBRARY") (part "Res-SMD"))
    )
    (comp (ref "R143")
      (value "Res")
      (footprint "RES-SMD-0603")
      (description "Resistor")
      (fields
        (field (name "MANUFACTURER") "Generic Components")
        (field (name "PUBLISHER") "Altium Hobart Technology Centre")
      )
      (libsource (lib "LIBRARY") (part "Res-SMD"))
    )
    (comp (ref "R144")
      (value "Res")
      (footprint "RES-SMD-0603")
      (description "Resistor")
      (fields
        (field (name "MANUFACTURER") "Generic Components")
        (field (name "PUBLISHER") "Altium Hobart Technology Centre")
      )
      (libsource (lib "LIBRARY") (part "Res-SMD"))
    )
    (comp (ref "R145")
      (value "Res")
      (footprint "RES-SMD-0603")
      (description "Resistor")
      (fields
        (field (name "MANUFACTURER") "Generic Components")
        (field (name "PUBLISHER") "Altium Hobart Technology Centre")
      )
      (libsource (lib "LIBRARY") (part "Res-SMD"))
    )
    (comp (ref "R146")
      (value "Res")
      (footprint "RES-SMD-0603")
      (description "Resistor")
      (fields
        (field (name "MANUFACTURER") "Generic Components")
        (field (name "PUBLISHER") "Altium Hobart Technology Centre")
      )
      (libsource (lib "LIBRARY") (part "Res-SMD"))
    )
    (comp (ref "R147")
      (value "Res")
      (footprint "RES-SMD-0603")
      (description "Resistor")
      (fields
        (field (name "MANUFACTURER") "Generic Components")
        (field (name "PUBLISHER") "Altium Hobart Technology Centre")
      )
      (libsource (lib "LIBRARY") (part "Res-SMD"))
    )
    (comp (ref "R148")
      (value "Res")
      (footprint "RES-SMD-0603")
      (description "Resistor")
      (fields
        (field (name "MANUFACTURER") "Generic Components")
        (field (name "PUBLISHER") "Altium Hobart Technology Centre")
      )
      (libsource (lib "LIBRARY") (part "Res-SMD"))
    )
    (comp (ref "R149")
      (value "Res")
      (footprint "RES-SMD-0603")
      (description "Resistor")
      (fields
        (field (name "MANUFACTURER") "Generic Components")
        (field (name "PUBLISHER") "Altium Hobart Technology Centre")
      )
      (libsource (lib "LIBRARY") (part "Res-SMD"))
    )
    (comp (ref "R150")
      (value "Res")
      (footprint "RES-SMD-0603")
      (description "Resistor")
      (fields
        (field (name "MANUFACTURER") "Generic Components")
        (field (name "PUBLISHER") "Altium Hobart Technology Centre")
      )
      (libsource (lib "LIBRARY") (part "Res-SMD"))
    )
    (comp (ref "R151")
      (value "Res")
      (footprint "RES-SMD-0603")
      (description "Resistor")
      (fields
        (field (name "MANUFACTURER") "Generic Components")
        (field (name "PUBLISHER") "Altium Hobart Technology Centre")
      )
      (libsource (lib "LIBRARY") (part "Res-SMD"))
    )
    (comp (ref "U6")
      (value "INA219BIDCNT")
      (footprint "SOT65P280X145-8N")
      (description "26V, 12-bit, i2c output current/voltage/power monitor 8-SOT-23 -40 to 125")
      (fields (field (name "MF") "Texas Instruments"))
      (libsource (lib "INA219BIDCNT") (part "INA219BIDCNT"))
    )
    (comp (ref "U7")
      (value "INA219BIDCNT")
      (footprint "SOT65P280X145-8N")
      (description "26V, 12-bit, i2c output current/voltage/power monitor 8-SOT-23 -40 to 125")
      (fields (field (name "MF") "Texas Instruments"))
      (libsource (lib "INA219BIDCNT") (part "INA219BIDCNT"))
    )
    (comp (ref "U8")
      (value "INA219BIDCNT")
      (footprint "SOT65P280X145-8N")
      (description "26V, 12-bit, i2c output current/voltage/power monitor 8-SOT-23 -40 to 125")
      (fields (field (name "MF") "Texas Instruments"))
      (libsource (lib "INA219BIDCNT") (part "INA219BIDCNT"))
    )
    (comp (ref "U9")
      (value "L9110")
      (footprint "DIP8")
      (description "Half-Bridge Driver")
      (libsource (lib "LIBRARY") (part "L9110"))
    )
    (comp (ref "U10")
      (value "L9110")
      (footprint "DIP8")
      (description "Half-Bridge Driver")
      (libsource (lib "LIBRARY") (part "L9110"))
    )
    (comp (ref "U11")
      (value "L9110")
      (footprint "DIP8")
      (description "Half-Bridge Driver")
      (libsource (lib "LIBRARY") (part "L9110"))
    )
    (comp (ref "U12")
      (value "INA219BIDCNT")
      (footprint "SOT65P280X145-8N")
      (description "26V, 12-bit, i2c output current/voltage/power monitor 8-SOT-23 -40 to 125")
      (fields (field (name "MF") "Texas Instruments"))
      (libsource (lib "INA219BIDCNT") (part "INA219BIDCNT"))
    )
    (comp (ref "U13")
      (value "INA219BIDCNT")
      (footprint "SOT65P280X145-8N")
      (description "26V, 12-bit, i2c output current/voltage/power monitor 8-SOT-23 -40 to 125")
      (fields (field (name "MF") "Texas Instruments"))
      (libsource (lib "INA219BIDCNT") (part "INA219BIDCNT"))
    )
    (comp (ref "U14")
      (value "INA219BIDCNT")
      (footprint "SOT65P280X145-8N")
      (description "26V, 12-bit, i2c output current/voltage/power monitor 8-SOT-23 -40 to 125")
      (fields (field (name "MF") "Texas Instruments"))
      (libsource (lib "INA219BIDCNT") (part "INA219BIDCNT"))
    )
    (comp (ref "U15")
      (value "L9110")
      (footprint "DIP8")
      (description "Half-Bridge Driver")
      (libsource (lib "LIBRARY") (part "L9110"))
    )
    (comp (ref "U16")
      (value "L9110")
      (footprint "DIP8")
      (description "Half-Bridge Driver")
      (libsource (lib "LIBRARY") (part "L9110"))
    )
    (comp (ref "U17")
      (value "L9110")
      (footprint "DIP8")
      (description "Half-Bridge Driver")
      (libsource (lib "LIBRARY") (part "L9110"))
    )
    (comp (ref "U18")
      (value "INA219BIDCNT")
      (footprint "SOT65P280X145-8N")
      (description "26V, 12-bit, i2c output current/voltage/power monitor 8-SOT-23 -40 to 125")
      (fields (field (name "MF") "Texas Instruments"))
      (libsource (lib "INA219BIDCNT") (part "INA219BIDCNT"))
    )
    (comp (ref "U19")
      (value "INA219BIDCNT")
      (footprint "SOT65P280X145-8N")
      (description "26V, 12-bit, i2c output current/voltage/power monitor 8-SOT-23 -40 to 125")
      (fields (field (name "MF") "Texas Instruments"))
      (libsource (lib "INA219BIDCNT") (part "INA219BIDCNT"))
    )
    (comp (ref "U20")
      (value "INA219BIDCNT")
      (footprint "SOT65P280X145-8N")
      (description "26V, 12-bit, i2c output current/voltage/power monitor 8-SOT-23 -40 to 125")
      (fields (field (name "MF") "Texas Instruments"))
      (libsource (lib "INA219BIDCNT") (part "INA219BIDCNT"))
    )
    (comp (ref "U21")
      (value "L9110")
      (footprint "DIP8")
      (description "Half-Bridge Driver")
      (libsource (lib "LIBRARY") (part "L9110"))
    )
    (comp (ref "U22")
      (value "L9110")
      (footprint "DIP8")
      (description "Half-Bridge Driver")
      (libsource (lib "LIBRARY") (part "L9110"))
    )
    (comp (ref "U23")
      (value "L9110")
      (footprint "DIP8")
      (description "Half-Bridge Driver")
      (libsource (lib "LIBRARY") (part "L9110"))
    )
    (comp (ref "U24")
      (value "INA219BIDCNT")
      (footprint "SOT65P280X145-8N")
      (description "26V, 12-bit, i2c output current/voltage/power monitor 8-SOT-23 -40 to 125")
      (fields (field (name "MF") "Texas Instruments"))
      (libsource (lib "INA219BIDCNT") (part "INA219BIDCNT"))
    )
    (comp (ref "U25")
      (value "INA219BIDCNT")
      (footprint "SOT65P280X145-8N")
      (description "26V, 12-bit, i2c output current/voltage/power monitor 8-SOT-23 -40 to 125")
      (fields (field (name "MF") "Texas Instruments"))
      (libsource (lib "INA219BIDCNT") (part "INA219BIDCNT"))
    )
    (comp (ref "U26")
      (value "INA219BIDCNT")
      (footprint "SOT65P280X145-8N")
      (description "26V, 12-bit, i2c output current/voltage/power monitor 8-SOT-23 -40 to 125")
      (fields (field (name "MF") "Texas Instruments"))
      (libsource (lib "INA219BIDCNT") (part "INA219BIDCNT"))
    )
    (comp (ref "U27")
      (value "L9110")
      (footprint "DIP8")
      (description "Half-Bridge Driver")
      (libsource (lib "LIBRARY") (part "L9110"))
    )
    (comp (ref "U28")
      (value "L9110")
      (footprint "DIP8")
      (description "Half-Bridge Driver")
      (libsource (lib "LIBRARY") (part "L9110"))
    )
    (comp (ref "U29")
      (value "L9110")
      (footprint "DIP8")
      (description "Half-Bridge Driver")
      (libsource (lib "LIBRARY") (part "L9110"))
    )
  )
  (nets
    (net (code "1") (name "/L1DOWN") (class "Default")
      (node (ref "R23") (pin "2") (pinfunction "2_2") (pintype "passive"))
      (node (ref "U9") (pin "7") (pinfunction "IB_7") (pintype "passive"))
    )
    (net (code "2") (name "/L1UP") (class "Default")
      (node (ref "R24") (pin "2") (pinfunction "2_2") (pintype "passive"))
      (node (ref "U9") (pin "6") (pinfunction "IA_6") (pintype "passive"))
    )
    (net (code "3") (name "/L2DOWN") (class "Default")
      (node (ref "R25") (pin "2") (pinfunction "2_2") (pintype "passive"))
      (node (ref "U10") (pin "7") (pinfunction "IB_7") (pintype "passive"))
    )
    (net (code "4") (name "/L2UP") (class "Default")
      (node (ref "R26") (pin "2") (pinfunction "2_2") (pintype "passive"))
      (node (ref "U10") (pin "6") (pinfunction "IA_6") (pintype "passive"))
    )
    (net (code "5") (name "/L3DOWN") (class "Default")
      (node (ref "R27") (pin "2") (pinfunction "2_2") (pintype "passive"))
      (node (ref "U11") (pin "7") (pinfunction "IB_7") (pintype "passive"))
    )
    (net (code "6") (name "/L3UP") (class "Default")
      (node (ref "R28") (pin "2") (pinfunction "2_2") (pintype "passive"))
      (node (ref "U11") (pin "6") (pinfunction "IA_6") (pintype "passive"))
    )
    (net (code "7") (name "/L4DOWN") (class "Default")
      (node (ref "R56") (pin "2") (pinfunction "2_2") (pintype "passive"))
      (node (ref "U15") (pin "7") (pinfunction "IB_7") (pintype "passive"))
    )
    (net (code "8") (name "/L4UP") (class "Default")
      (node (ref "R57") (pin "2") (pinfunction "2_2") (pintype "passive"))
      (node (ref "U15") (pin "6") (pinfunction "IA_6") (pintype "passive"))
    )
    (net (code "9") (name "/L5DOWN") (class "Default")
      (node (ref "R58") (pin "2") (pinfunction "2_2") (pintype "passive"))
      (node (ref "U16") (pin "7") (pinfunction "IB_7") (pintype "passive"))
    )
    (net (code "10") (name "/L5UP") (class "Default")
      (node (ref "R59") (pin "2") (pinfunction "2_2") (pintype "passive"))
      (node (ref "U16") (pin "6") (pinfunction "IA_6") (pintype "passive"))
    )
    (net (code "11") (name "/L6DOWN") (class "Default")
      (node (ref "R60") (pin "2") (pinfunction "2_2") (pintype "passive"))
      (node (ref "U17") (pin "7") (pinfunction "IB_7") (pintype "passive"))
    )
    (net (code "12") (name "/L6UP") (class "Default")
      (node (ref "R61") (pin "2") (pinfunction "2_2") (pintype "passive"))
      (node (ref "U17") (pin "6") (pinfunction "IA_6") (pintype "passive"))
    )
    (net (code "13") (name "/L7DOWN") (class "Default")
      (node (ref "R89") (pin "2") (pinfunction "2_2") (pintype "passive"))
      (node (ref "U21") (pin "7") (pinfunction "IB_7") (pintype "passive"))
    )
    (net (code "14") (name "/L7UP") (class "Default")
      (node (ref "R90") (pin "2") (pinfunction "2_2") (pintype "passive"))
      (node (ref "U21") (pin "6") (pinfunction "IA_6") (pintype "passive"))
    )
    (net (code "15") (name "/L8DOWN") (class "Default")
      (node (ref "R91") (pin "2") (pinfunction "2_2") (pintype "passive"))
      (node (ref "U22") (pin "7") (pinfunction "IB_7") (pintype "passive"))
    )
    (net (code "16") (name "/L8UP") (class "Default")
      (node (ref "R92") (pin "2") (pinfunction "2_2") (pintype "passive"))
      (node (ref "U22") (pin "6") (pinfunction "IA_6") (pintype "passive"))
    )
    (net (code "17") (name "/L9DOWN") (class "Default")
      (node (ref "R93") (pin "2") (pinfunction "2_2") (pintype "passive"))
      (node (ref "U23") (pin "7") (pinfunction "IB_7") (pintype "passive"))
    )
    (net (code "18") (name "/L9UP") (class "Default")
      (node (ref "R94") (pin "2") (pinfunction "2_2") (pintype "passive"))
      (node (ref "U23") (pin "6") (pinfunction "IA_6") (pintype "passive"))
    )
    (net (code "19") (name "/L10DOWN") (class "Default")
      (node (ref "R122") (pin "2") (pinfunction "2_2") (pintype "passive"))
      (node (ref "U27") (pin "7") (pinfunction "IB_7") (pintype "passive"))
    )
    (net (code "20") (name "/L10UP") (class "Default")
      (node (ref "R123") (pin "2") (pinfunction "2_2") (pintype "passive"))
      (node (ref "U27") (pin "6") (pinfunction "IA_6") (pintype "passive"))
    )
    (net (code "21") (name "/L11DOWN") (class "Default")
      (node (ref "R124") (pin "2") (pinfunction "2_2") (pintype "passive"))
      (node (ref "U28") (pin "7") (pinfunction "IB_7") (pintype "passive"))
    )
    (net (code "22") (name "/L11UP") (class "Default")
      (node (ref "R125") (pin "2") (pinfunction "2_2") (pintype "passive"))
      (node (ref "U28") (pin "6") (pinfunction "IA_6") (pintype "passive"))
    )
    (net (code "23") (name "/L12DOWN") (class "Default")
      (node (ref "R126") (pin "2") (pinfunction "2_2") (pintype "passive"))
      (node (ref "U29") (pin "7") (pinfunction "IB_7") (pintype "passive"))
    )
    (net (code "24") (name "/L12UP") (class "Default")
      (node (ref "R127") (pin "2") (pinfunction "2_2") (pintype "passive"))
      (node (ref "U29") (pin "6") (pinfunction "IA_6") (pintype "passive"))
    )
    (net (code "25") (name "3V3_1") (class "Default")
      (node (ref "R105") (pin "1") (pinfunction "1_1") (pintype "passive"))
      (node (ref "R107") (pin "1") (pinfunction "1_1") (pintype "passive"))
      (node (ref "R109") (pin "1") (pinfunction "1_1") (pintype "passive"))
      (node (ref "R110") (pin "1") (pinfunction "1_1") (pintype "passive"))
      (node (ref "R112") (pin "1") (pinfunction "1_1") (pintype "passive"))
      (node (ref "R114") (pin "1") (pinfunction "1_1") (pintype "passive"))
      (node (ref "R138") (pin "1") (pinfunction "1_1") (pintype "passive"))
      (node (ref "R140") (pin "1") (pinfunction "1_1") (pintype "passive"))
      (node (ref "R142") (pin "1") (pinfunction "1_1") (pintype "passive"))
      (node (ref "R143") (pin "1") (pinfunction "1_1") (pintype "passive"))
      (node (ref "R145") (pin "1") (pinfunction "1_1") (pintype "passive"))
      (node (ref "R147") (pin "1") (pinfunction "1_1") (pintype "passive"))
      (node (ref "R39") (pin "1") (pinfunction "1_1") (pintype "passive"))
      (node (ref "R41") (pin "1") (pinfunction "1_1") (pintype "passive"))
      (node (ref "R43") (pin "1") (pinfunction "1_1") (pintype "passive"))
      (node (ref "R44") (pin "1") (pinfunction "1_1") (pintype "passive"))
      (node (ref "R46") (pin "1") (pinfunction "1_1") (pintype "passive"))
      (node (ref "R48") (pin "1") (pinfunction "1_1") (pintype "passive"))
      (node (ref "R72") (pin "1") (pinfunction "1_1") (pintype "passive"))
      (node (ref "R74") (pin "1") (pinfunction "1_1") (pintype "passive"))
      (node (ref "R76") (pin "1") (pinfunction "1_1") (pintype "passive"))
      (node (ref "R77") (pin "1") (pinfunction "1_1") (pintype "passive"))
      (node (ref "R79") (pin "1") (pinfunction "1_1") (pintype "passive"))
      (node (ref "R81") (pin "1") (pinfunction "1_1") (pintype "passive"))
      (node (ref "U12") (pin "4") (pinfunction "VS_4") (pintype "power_in"))
      (node (ref "U13") (pin "4") (pinfunction "VS_4") (pintype "power_in"))
      (node (ref "U14") (pin "4") (pinfunction "VS_4") (pintype "power_in"))
      (node (ref "U18") (pin "4") (pinfunction "VS_4") (pintype "power_in"))
      (node (ref "U19") (pin "4") (pinfunction "VS_4") (pintype "power_in"))
      (node (ref "U20") (pin "4") (pinfunction "VS_4") (pintype "power_in"))
      (node (ref "U24") (pin "4") (pinfunction "VS_4") (pintype "power_in"))
      (node (ref "U25") (pin "4") (pinfunction "VS_4") (pintype "power_in"))
      (node (ref "U26") (pin "4") (pinfunction "VS_4") (pintype "power_in"))
      (node (ref "U6") (pin "4") (pinfunction "VS_4") (pintype "power_in"))
      (node (ref "U7") (pin "4") (pinfunction "VS_4") (pintype "power_in"))
      (node (ref "U8") (pin "4") (pinfunction "VS_4") (pintype "power_in"))
    )
    (net (code "26") (name "12V") (class "Default")
      (node (ref "R119") (pin "1") (pinfunction "1_1") (pintype "passive"))
      (node (ref "R120") (pin "1") (pinfunction "1_1") (pintype "passive"))
      (node (ref "R121") (pin "1") (pinfunction "1_1") (pintype "passive"))
      (node (ref "R122") (pin "1") (pinfunction "1_1") (pintype "passive"))
      (node (ref "R123") (pin "1") (pinfunction "1_1") (pintype "passive"))
      (node (ref "R124") (pin "1") (pinfunction "1_1") (pintype "passive"))
      (node (ref "R125") (pin "1") (pinfunction "1_1") (pintype "passive"))
      (node (ref "R126") (pin "1") (pinfunction "1_1") (pintype "passive"))
      (node (ref "R127") (pin "1") (pinfunction "1_1") (pintype "passive"))
      (node (ref "R20") (pin "1") (pinfunction "1_1") (pintype "passive"))
      (node (ref "R21") (pin "1") (pinfunction "1_1") (pintype "passive"))
      (node (ref "R22") (pin "1") (pinfunction "1_1") (pintype "passive"))
      (node (ref "R23") (pin "1") (pinfunction "1_1") (pintype "passive"))
      (node (ref "R24") (pin "1") (pinfunction "1_1") (pintype "passive"))
      (node (ref "R25") (pin "1") (pinfunction "1_1") (pintype "passive"))
      (node (ref "R26") (pin "1") (pinfunction "1_1") (pintype "passive"))
      (node (ref "R27") (pin "1") (pinfunction "1_1") (pintype "passive"))
      (node (ref "R28") (pin "1") (pinfunction "1_1") (pintype "passive"))
      (node (ref "R53") (pin "1") (pinfunction "1_1") (pintype "passive"))
      (node (ref "R54") (pin "1") (pinfunction "1_1") (pintype "passive"))
      (node (ref "R55") (pin "1") (pinfunction "1_1") (pintype "passive"))
      (node (ref "R56") (pin "1") (pinfunction "1_1") (pintype "passive"))
      (node (ref "R57") (pin "1") (pinfunction "1_1") (pintype "passive"))
      (node (ref "R58") (pin "1") (pinfunction "1_1") (pintype "passive"))
      (node (ref "R59") (pin "1") (pinfunction "1_1") (pintype "passive"))
      (node (ref "R60") (pin "1") (pinfunction "1_1") (pintype "passive"))
      (node (ref "R61") (pin "1") (pinfunction "1_1") (pintype "passive"))
      (node (ref "R86") (pin "1") (pinfunction "1_1") (pintype "passive"))
      (node (ref "R87") (pin "1") (pinfunction "1_1") (pintype "passive"))
      (node (ref "R88") (pin "1") (pinfunction "1_1") (pintype "passive"))
      (node (ref "R89") (pin "1") (pinfunction "1_1") (pintype "passive"))
      (node (ref "R90") (pin "1") (pinfunction "1_1") (pintype "passive"))
      (node (ref "R91") (pin "1") (pinfunction "1_1") (pintype "passive"))
      (node (ref "R92") (pin "1") (pinfunction "1_1") (pintype "passive"))
      (node (ref "R93") (pin "1") (pinfunction "1_1") (pintype "passive"))
      (node (ref "R94") (pin "1") (pinfunction "1_1") (pintype "passive"))
      (node (ref "U12") (pin "1") (pinfunction "VIN+_1") (pintype "input"))
      (node (ref "U13") (pin "1") (pinfunction "VIN+_1") (pintype "input"))
      (node (ref "U14") (pin "1") (pinfunction "VIN+_1") (pintype "input"))
      (node (ref "U18") (pin "1") (pinfunction "VIN+_1") (pintype "input"))
      (node (ref "U19") (pin "1") (pinfunction "VIN+_1") (pintype "input"))
      (node (ref "U20") (pin "1") (pinfunction "VIN+_1") (pintype "input"))
      (node (ref "U24") (pin "1") (pinfunction "VIN+_1") (pintype "input"))
      (node (ref "U25") (pin "1") (pinfunction "VIN+_1") (pintype "input"))
      (node (ref "U26") (pin "1") (pinfunction "VIN+_1") (pintype "input"))
      (node (ref "U6") (pin "1") (pinfunction "VIN+_1") (pintype "input"))
      (node (ref "U7") (pin "1") (pinfunction "VIN+_1") (pintype "input"))
      (node (ref "U8") (pin "1") (pinfunction "VIN+_1") (pintype "input"))
    )
    (net (code "27") (name "A0_1") (class "Default")
      (node (ref "R32") (pin "2") (pinfunction "2_2") (pintype "passive"))
      (node (ref "R38") (pin "2") (pinfunction "2_2") (pintype "passive"))
      (node (ref "R44") (pin "2") (pinfunction "2_2") (pintype "passive"))
      (node (ref "R50") (pin "2") (pinfunction "2_2") (pintype "passive"))
      (node (ref "U6") (pin "7") (pinfunction "A0_7") (pintype "input"))
    )
    (net (code "28") (name "A0_2") (class "Default")
      (node (ref "R34") (pin "2") (pinfunction "2_2") (pintype "passive"))
      (node (ref "R40") (pin "2") (pinfunction "2_2") (pintype "passive"))
      (node (ref "R46") (pin "2") (pinfunction "2_2") (pintype "passive"))
      (node (ref "R51") (pin "2") (pinfunction "2_2") (pintype "passive"))
      (node (ref "U7") (pin "7") (pinfunction "A0_7") (pintype "input"))
    )
    (net (code "29") (name "A0_3") (class "Default")
      (node (ref "R36") (pin "2") (pinfunction "2_2") (pintype "passive"))
      (node (ref "R42") (pin "2") (pinfunction "2_2") (pintype "passive"))
      (node (ref "R48") (pin "2") (pinfunction "2_2") (pintype "passive"))
      (node (ref "R52") (pin "2") (pinfunction "2_2") (pintype "passive"))
      (node (ref "U8") (pin "7") (pinfunction "A0_7") (pintype "input"))
    )
    (net (code "30") (name "A0_4") (class "Default")
      (node (ref "R65") (pin "2") (pinfunction "2_2") (pintype "passive"))
      (node (ref "R71") (pin "2") (pinfunction "2_2") (pintype "passive"))
      (node (ref "R77") (pin "2") (pinfunction "2_2") (pintype "passive"))
      (node (ref "R83") (pin "2") (pinfunction "2_2") (pintype "passive"))
      (node (ref "U12") (pin "7") (pinfunction "A0_7") (pintype "input"))
    )
    (net (code "31") (name "A0_5") (class "Default")
      (node (ref "R67") (pin "2") (pinfunction "2_2") (pintype "passive"))
      (node (ref "R73") (pin "2") (pinfunction "2_2") (pintype "passive"))
      (node (ref "R79") (pin "2") (pinfunction "2_2") (pintype "passive"))
      (node (ref "R84") (pin "2") (pinfunction "2_2") (pintype "passive"))
      (node (ref "U13") (pin "7") (pinfunction "A0_7") (pintype "input"))
    )
    (net (code "32") (name "A0_6") (class "Default")
      (node (ref "R69") (pin "2") (pinfunction "2_2") (pintype "passive"))
      (node (ref "R75") (pin "2") (pinfunction "2_2") (pintype "passive"))
      (node (ref "R81") (pin "2") (pinfunction "2_2") (pintype "passive"))
      (node (ref "R85") (pin "2") (pinfunction "2_2") (pintype "passive"))
      (node (ref "U14") (pin "7") (pinfunction "A0_7") (pintype "input"))
    )
    (net (code "33") (name "A0_7") (class "Default")
      (node (ref "R104") (pin "2") (pinfunction "2_2") (pintype "passive"))
      (node (ref "R110") (pin "2") (pinfunction "2_2") (pintype "passive"))
      (node (ref "R116") (pin "2") (pinfunction "2_2") (pintype "passive"))
      (node (ref "R98") (pin "2") (pinfunction "2_2") (pintype "passive"))
      (node (ref "U18") (pin "7") (pinfunction "A0_7") (pintype "input"))
    )
    (net (code "34") (name "A0_8") (class "Default")
      (node (ref "R100") (pin "2") (pinfunction "2_2") (pintype "passive"))
      (node (ref "R106") (pin "2") (pinfunction "2_2") (pintype "passive"))
      (node (ref "R112") (pin "2") (pinfunction "2_2") (pintype "passive"))
      (node (ref "R117") (pin "2") (pinfunction "2_2") (pintype "passive"))
      (node (ref "U19") (pin "7") (pinfunction "A0_7") (pintype "input"))
    )
    (net (code "35") (name "A0_9") (class "Default")
      (node (ref "R102") (pin "2") (pinfunction "2_2") (pintype "passive"))
      (node (ref "R108") (pin "2") (pinfunction "2_2") (pintype "passive"))
      (node (ref "R114") (pin "2") (pinfunction "2_2") (pintype "passive"))
      (node (ref "R118") (pin "2") (pinfunction "2_2") (pintype "passive"))
      (node (ref "U20") (pin "7") (pinfunction "A0_7") (pintype "input"))
    )
    (net (code "36") (name "A0_10") (class "Default")
      (node (ref "R131") (pin "2") (pinfunction "2_2") (pintype "passive"))
      (node (ref "R137") (pin "2") (pinfunction "2_2") (pintype "passive"))
      (node (ref "R143") (pin "2") (pinfunction "2_2") (pintype "passive"))
      (node (ref "R149") (pin "2") (pinfunction "2_2") (pintype "passive"))
      (node (ref "U24") (pin "7") (pinfunction "A0_7") (pintype "input"))
    )
    (net (code "37") (name "A0_11") (class "Default")
      (node (ref "R133") (pin "2") (pinfunction "2_2") (pintype "passive"))
      (node (ref "R139") (pin "2") (pinfunction "2_2") (pintype "passive"))
      (node (ref "R145") (pin "2") (pinfunction "2_2") (pintype "passive"))
      (node (ref "R150") (pin "2") (pinfunction "2_2") (pintype "passive"))
      (node (ref "U25") (pin "7") (pinfunction "A0_7") (pintype "input"))
    )
    (net (code "38") (name "A0_12") (class "Default")
      (node (ref "R135") (pin "2") (pinfunction "2_2") (pintype "passive"))
      (node (ref "R141") (pin "2") (pinfunction "2_2") (pintype "passive"))
      (node (ref "R147") (pin "2") (pinfunction "2_2") (pintype "passive"))
      (node (ref "R151") (pin "2") (pinfunction "2_2") (pintype "passive"))
      (node (ref "U26") (pin "7") (pinfunction "A0_7") (pintype "input"))
    )
    (net (code "39") (name "A1_1") (class "Default")
      (node (ref "R29") (pin "2") (pinfunction "2_2") (pintype "passive"))
      (node (ref "R33") (pin "2") (pinfunction "2_2") (pintype "passive"))
      (node (ref "R39") (pin "2") (pinfunction "2_2") (pintype "passive"))
      (node (ref "R45") (pin "2") (pinfunction "2_2") (pintype "passive"))
      (node (ref "U6") (pin "8") (pinfunction "A1_8") (pintype "input"))
    )
    (net (code "40") (name "A1_2") (class "Default")
      (node (ref "R30") (pin "2") (pinfunction "2_2") (pintype "passive"))
      (node (ref "R35") (pin "2") (pinfunction "2_2") (pintype "passive"))
      (node (ref "R41") (pin "2") (pinfunction "2_2") (pintype "passive"))
      (node (ref "R47") (pin "2") (pinfunction "2_2") (pintype "passive"))
      (node (ref "U7") (pin "8") (pinfunction "A1_8") (pintype "input"))
    )
    (net (code "41") (name "A1_3") (class "Default")
      (node (ref "R31") (pin "2") (pinfunction "2_2") (pintype "passive"))
      (node (ref "R37") (pin "2") (pinfunction "2_2") (pintype "passive"))
      (node (ref "R43") (pin "2") (pinfunction "2_2") (pintype "passive"))
      (node (ref "R49") (pin "2") (pinfunction "2_2") (pintype "passive"))
      (node (ref "U8") (pin "8") (pinfunction "A1_8") (pintype "input"))
    )
    (net (code "42") (name "A1_4") (class "Default")
      (node (ref "R62") (pin "2") (pinfunction "2_2") (pintype "passive"))
      (node (ref "R66") (pin "2") (pinfunction "2_2") (pintype "passive"))
      (node (ref "R72") (pin "2") (pinfunction "2_2") (pintype "passive"))
      (node (ref "R78") (pin "2") (pinfunction "2_2") (pintype "passive"))
      (node (ref "U12") (pin "8") (pinfunction "A1_8") (pintype "input"))
    )
    (net (code "43") (name "A1_5") (class "Default")
      (node (ref "R63") (pin "2") (pinfunction "2_2") (pintype "passive"))
      (node (ref "R68") (pin "2") (pinfunction "2_2") (pintype "passive"))
      (node (ref "R74") (pin "2") (pinfunction "2_2") (pintype "passive"))
      (node (ref "R80") (pin "2") (pinfunction "2_2") (pintype "passive"))
      (node (ref "U13") (pin "8") (pinfunction "A1_8") (pintype "input"))
    )
    (net (code "44") (name "A1_6") (class "Default")
      (node (ref "R64") (pin "2") (pinfunction "2_2") (pintype "passive"))
      (node (ref "R70") (pin "2") (pinfunction "2_2") (pintype "passive"))
      (node (ref "R76") (pin "2") (pinfunction "2_2") (pintype "passive"))
      (node (ref "R82") (pin "2") (pinfunction "2_2") (pintype "passive"))
      (node (ref "U14") (pin "8") (pinfunction "A1_8") (pintype "input"))
    )
    (net (code "45") (name "A1_7") (class "Default")
      (node (ref "R105") (pin "2") (pinfunction "2_2") (pintype "passive"))
      (node (ref "R111") (pin "2") (pinfunction "2_2") (pintype "passive"))
      (node (ref "R95") (pin "2") (pinfunction "2_2") (pintype "passive"))
      (node (ref "R99") (pin "2") (pinfunction "2_2") (pintype "passive"))
      (node (ref "U18") (pin "8") (pinfunction "A1_8") (pintype "input"))
    )
    (net (code "46") (name "A1_8") (class "Default")
      (node (ref "R101") (pin "2") (pinfunction "2_2") (pintype "passive"))
      (node (ref "R107") (pin "2") (pinfunction "2_2") (pintype "passive"))
      (node (ref "R113") (pin "2") (pinfunction "2_2") (pintype "passive"))
      (node (ref "R96") (pin "2") (pinfunction "2_2") (pintype "passive"))
      (node (ref "U19") (pin "8") (pinfunction "A1_8") (pintype "input"))
    )
    (net (code "47") (name "A1_9") (class "Default")
      (node (ref "R103") (pin "2") (pinfunction "2_2") (pintype "passive"))
      (node (ref "R109") (pin "2") (pinfunction "2_2") (pintype "passive"))
      (node (ref "R115") (pin "2") (pinfunction "2_2") (pintype "passive"))
      (node (ref "R97") (pin "2") (pinfunction "2_2") (pintype "passive"))
      (node (ref "U20") (pin "8") (pinfunction "A1_8") (pintype "input"))
    )
    (net (code "48") (name "A1_10") (class "Default")
      (node (ref "R128") (pin "2") (pinfunction "2_2") (pintype "passive"))
      (node (ref "R132") (pin "2") (pinfunction "2_2") (pintype "passive"))
      (node (ref "R138") (pin "2") (pinfunction "2_2") (pintype "passive"))
      (node (ref "R144") (pin "2") (pinfunction "2_2") (pintype "passive"))
      (node (ref "U24") (pin "8") (pinfunction "A1_8") (pintype "input"))
    )
    (net (code "49") (name "A1_11") (class "Default")
      (node (ref "R129") (pin "2") (pinfunction "2_2") (pintype "passive"))
      (node (ref "R134") (pin "2") (pinfunction "2_2") (pintype "passive"))
      (node (ref "R140") (pin "2") (pinfunction "2_2") (pintype "passive"))
      (node (ref "R146") (pin "2") (pinfunction "2_2") (pintype "passive"))
      (node (ref "U25") (pin "8") (pinfunction "A1_8") (pintype "input"))
    )
    (net (code "50") (name "A1_12") (class "Default")
      (node (ref "R130") (pin "2") (pinfunction "2_2") (pintype "passive"))
      (node (ref "R136") (pin "2") (pinfunction "2_2") (pintype "passive"))
      (node (ref "R142") (pin "2") (pinfunction "2_2") (pintype "passive"))
      (node (ref "R148") (pin "2") (pinfunction "2_2") (pintype "passive"))
      (node (ref "U26") (pin "8") (pinfunction "A1_8") (pintype "input"))
    )
    (net (code "51") (name "GND") (class "Default")
      (node (ref "R111") (pin "1") (pinfunction "1_1") (pintype "passive"))
      (node (ref "R113") (pin "1") (pinfunction "1_1") (pintype "passive"))
      (node (ref "R115") (pin "1") (pinfunction "1_1") (pintype "passive"))
      (node (ref "R116") (pin "1") (pinfunction "1_1") (pintype "passive"))
      (node (ref "R117") (pin "1") (pinfunction "1_1") (pintype "passive"))
      (node (ref "R118") (pin "1") (pinfunction "1_1") (pintype "passive"))
      (node (ref "R144") (pin "1") (pinfunction "1_1") (pintype "passive"))
      (node (ref "R146") (pin "1") (pinfunction "1_1") (pintype "passive"))
      (node (ref "R148") (pin "1") (pinfunction "1_1") (pintype "passive"))
      (node (ref "R149") (pin "1") (pinfunction "1_1") (pintype "passive"))
      (node (ref "R150") (pin "1") (pinfunction "1_1") (pintype "passive"))
      (node (ref "R151") (pin "1") (pinfunction "1_1") (pintype "passive"))
      (node (ref "R45") (pin "1") (pinfunction "1_1") (pintype "passive"))
      (node (ref "R47") (pin "1") (pinfunction "1_1") (pintype "passive"))
      (node (ref "R49") (pin "1") (pinfunction "1_1") (pintype "passive"))
      (node (ref "R50") (pin "1") (pinfunction "1_1") (pintype "passive"))
      (node (ref "R51") (pin "1") (pinfunction "1_1") (pintype "passive"))
      (node (ref "R52") (pin "1") (pinfunction "1_1") (pintype "passive"))
      (node (ref "R78") (pin "1") (pinfunction "1_1") (pintype "passive"))
      (node (ref "R80") (pin "1") (pinfunction "1_1") (pintype "passive"))
      (node (ref "R82") (pin "1") (pinfunction "1_1") (pintype "passive"))
      (node (ref "R83") (pin "1") (pinfunction "1_1") (pintype "passive"))
      (node (ref "R84") (pin "1") (pinfunction "1_1") (pintype "passive"))
      (node (ref "R85") (pin "1") (pinfunction "1_1") (pintype "passive"))
      (node (ref "U10") (pin "5") (pinfunction "-_5") (pintype "passive"))
      (node (ref "U10") (pin "8") (pinfunction "-_8") (pintype "passive"))
      (node (ref "U11") (pin "5") (pinfunction "-_5") (pintype "passive"))
      (node (ref "U11") (pin "8") (pinfunction "-_8") (pintype "passive"))
      (node (ref "U12") (pin "3") (pinfunction "GND_3") (pintype "power_in"))
      (node (ref "U13") (pin "3") (pinfunction "GND_3") (pintype "power_in"))
      (node (ref "U14") (pin "3") (pinfunction "GND_3") (pintype "power_in"))
      (node (ref "U15") (pin "5") (pinfunction "-_5") (pintype "passive"))
      (node (ref "U15") (pin "8") (pinfunction "-_8") (pintype "passive"))
      (node (ref "U16") (pin "5") (pinfunction "-_5") (pintype "passive"))
      (node (ref "U16") (pin "8") (pinfunction "-_8") (pintype "passive"))
      (node (ref "U17") (pin "5") (pinfunction "-_5") (pintype "passive"))
      (node (ref "U17") (pin "8") (pinfunction "-_8") (pintype "passive"))
      (node (ref "U18") (pin "3") (pinfunction "GND_3") (pintype "power_in"))
      (node (ref "U19") (pin "3") (pinfunction "GND_3") (pintype "power_in"))
      (node (ref "U20") (pin "3") (pinfunction "GND_3") (pintype "power_in"))
      (node (ref "U21") (pin "5") (pinfunction "-_5") (pintype "passive"))
      (node (ref "U21") (pin "8") (pinfunction "-_8") (pintype "passive"))
      (node (ref "U22") (pin "5") (pinfunction "-_5") (pintype "passive"))
      (node (ref "U22") (pin "8") (pinfunction "-_8") (pintype "passive"))
      (node (ref "U23") (pin "5") (pinfunction "-_5") (pintype "passive"))
      (node (ref "U23") (pin "8") (pinfunction "-_8") (pintype "passive"))
      (node (ref "U24") (pin "3") (pinfunction "GND_3") (pintype "power_in"))
      (node (ref "U25") (pin "3") (pinfunction "GND_3") (pintype "power_in"))
      (node (ref "U26") (pin "3") (pinfunction "GND_3") (pintype "power_in"))
      (node (ref "U27") (pin "5") (pinfunction "-_5") (pintype "passive"))
      (node (ref "U27") (pin "8") (pinfunction "-_8") (pintype "passive"))
      (node (ref "U28") (pin "5") (pinfunction "-_5") (pintype "passive"))
      (node (ref "U28") (pin "8") (pinfunction "-_8") (pintype "passive"))
      (node (ref "U29") (pin "5") (pinfunction "-_5") (pintype "passive"))
      (node (ref "U29") (pin "8") (pinfunction "-_8") (pintype "passive"))
      (node (ref "U6") (pin "3") (pinfunction "GND_3") (pintype "power_in"))
      (node (ref "U7") (pin "3") (pinfunction "GND_3") (pintype "power_in"))
      (node (ref "U8") (pin "3") (pinfunction "GND_3") (pintype "power_in"))
      (node (ref "U9") (pin "5") (pinfunction "-_5") (pintype "passive"))
      (node (ref "U9") (pin "8") (pinfunction "-_8") (pintype "passive"))
    )
    (net (code "52") (name "Net-(U6-VIN-)") (class "Default")
      (node (ref "R20") (pin "2") (pinfunction "2_2") (pintype "passive"))
      (node (ref "U6") (pin "2") (pinfunction "VIN-_2") (pintype "input"))
      (node (ref "U9") (pin "2") (pinfunction "+_2") (pintype "passive"))
      (node (ref "U9") (pin "3") (pinfunction "+_3") (pintype "passive"))
    )
    (net (code "53") (name "Net-(U7-VIN-)") (class "Default")
      (node (ref "R21") (pin "2") (pinfunction "2_2") (pintype "passive"))
      (node (ref "U10") (pin "2") (pinfunction "+_2") (pintype "passive"))
      (node (ref "U10") (pin "3") (pinfunction "+_3") (pintype "passive"))
      (node (ref "U7") (pin "2") (pinfunction "VIN-_2") (pintype "input"))
    )
    (net (code "54") (name "Net-(U8-VIN-)") (class "Default")
      (node (ref "R22") (pin "2") (pinfunction "2_2") (pintype "passive"))
      (node (ref "U11") (pin "2") (pinfunction "+_2") (pintype "passive"))
      (node (ref "U11") (pin "3") (pinfunction "+_3") (pintype "passive"))
      (node (ref "U8") (pin "2") (pinfunction "VIN-_2") (pintype "input"))
    )
    (net (code "55") (name "Net-(U9-OA)") (class "Default")
      (node (ref "C1") (pin "1") (pinfunction "1_1") (pintype "passive"))
      (node (ref "J3") (pin "1") (pinfunction "1_1") (pintype "passive"))
      (node (ref "U9") (pin "1") (pinfunction "OA_1") (pintype "passive"))
    )
    (net (code "56") (name "Net-(U9-OB)") (class "Default")
      (node (ref "C1") (pin "2") (pinfunction "2_2") (pintype "passive"))
      (node (ref "J3") (pin "2") (pinfunction "2_2") (pintype "passive"))
      (node (ref "U9") (pin "4") (pinfunction "OB_4") (pintype "passive"))
    )
    (net (code "57") (name "Net-(U10-OA)") (class "Default")
      (node (ref "C2") (pin "1") (pinfunction "1_1") (pintype "passive"))
      (node (ref "J4") (pin "1") (pinfunction "1_1") (pintype "passive"))
      (node (ref "U10") (pin "1") (pinfunction "OA_1") (pintype "passive"))
    )
    (net (code "58") (name "Net-(U10-OB)") (class "Default")
      (node (ref "C2") (pin "2") (pinfunction "2_2") (pintype "passive"))
      (node (ref "J4") (pin "2") (pinfunction "2_2") (pintype "passive"))
      (node (ref "U10") (pin "4") (pinfunction "OB_4") (pintype "passive"))
    )
    (net (code "59") (name "Net-(U11-OA)") (class "Default")
      (node (ref "C3") (pin "1") (pinfunction "1_1") (pintype "passive"))
      (node (ref "J5") (pin "1") (pinfunction "1_1") (pintype "passive"))
      (node (ref "U11") (pin "1") (pinfunction "OA_1") (pintype "passive"))
    )
    (net (code "60") (name "Net-(U11-OB)") (class "Default")
      (node (ref "C3") (pin "2") (pinfunction "2_2") (pintype "passive"))
      (node (ref "J5") (pin "2") (pinfunction "2_2") (pintype "passive"))
      (node (ref "U11") (pin "4") (pinfunction "OB_4") (pintype "passive"))
    )
    (net (code "61") (name "Net-(U12-VIN-)") (class "Default")
      (node (ref "R53") (pin "2") (pinfunction "2_2") (pintype "passive"))
      (node (ref "U12") (pin "2") (pinfunction "VIN-_2") (pintype "input"))
      (node (ref "U15") (pin "2") (pinfunction "+_2") (pintype "passive"))
      (node (ref "U15") (pin "3") (pinfunction "+_3") (pintype "passive"))
    )
    (net (code "62") (name "Net-(U13-VIN-)") (class "Default")
      (node (ref "R54") (pin "2") (pinfunction "2_2") (pintype "passive"))
      (node (ref "U13") (pin "2") (pinfunction "VIN-_2") (pintype "input"))
      (node (ref "U16") (pin "2") (pinfunction "+_2") (pintype "passive"))
      (node (ref "U16") (pin "3") (pinfunction "+_3") (pintype "passive"))
    )
    (net (code "63") (name "Net-(U14-VIN-)") (class "Default")
      (node (ref "R55") (pin "2") (pinfunction "2_2") (pintype "passive"))
      (node (ref "U14") (pin "2") (pinfunction "VIN-_2") (pintype "input"))
      (node (ref "U17") (pin "2") (pinfunction "+_2") (pintype "passive"))
      (node (ref "U17") (pin "3") (pinfunction "+_3") (pintype "passive"))
    )
    (net (code "64") (name "Net-(U15-OA)") (class "Default")
      (node (ref "C4") (pin "1") (pinfunction "1_1") (pintype "passive"))
      (node (ref "J6") (pin "1") (pinfunction "1_1") (pintype "passive"))
      (node (ref "U15") (pin "1") (pinfunction "OA_1") (pintype "passive"))
    )
    (net (code "65") (name "Net-(U15-OB)") (class "Default")
      (node (ref "C4") (pin "2") (pinfunction "2_2") (pintype "passive"))
      (node (ref "J6") (pin "2") (pinfunction "2_2") (pintype "passive"))
      (node (ref "U15") (pin "4") (pinfunction "OB_4") (pintype "passive"))
    )
    (net (code "66") (name "Net-(U16-OA)") (class "Default")
      (node (ref "C5") (pin "1") (pinfunction "1_1") (pintype "passive"))
      (node (ref "J7") (pin "1") (pinfunction "1_1") (pintype "passive"))
      (node (ref "U16") (pin "1") (pinfunction "OA_1") (pintype "passive"))
    )
    (net (code "67") (name "Net-(U16-OB)") (class "Default")
      (node (ref "C5") (pin "2") (pinfunction "2_2") (pintype "passive"))
      (node (ref "J7") (pin "2") (pinfunction "2_2") (pintype "passive"))
      (node (ref "U16") (pin "4") (pinfunction "OB_4") (pintype "passive"))
    )
    (net (code "68") (name "Net-(U17-OA)") (class "Default")
      (node (ref "C6") (pin "1") (pinfunction "1_1") (pintype "passive"))
      (node (ref "J8") (pin "1") (pinfunction "1_1") (pintype "passive"))
      (node (ref "U17") (pin "1") (pinfunction "OA_1") (pintype "passive"))
    )
    (net (code "69") (name "Net-(U17-OB)") (class "Default")
      (node (ref "C6") (pin "2") (pinfunction "2_2") (pintype "passive"))
      (node (ref "J8") (pin "2") (pinfunction "2_2") (pintype "passive"))
      (node (ref "U17") (pin "4") (pinfunction "OB_4") (pintype "passive"))
    )
    (net (code "70") (name "Net-(U18-VIN-)") (class "Default")
      (node (ref "R86") (pin "2") (pinfunction "2_2") (pintype "passive"))
      (node (ref "U18") (pin "2") (pinfunction "VIN-_2") (pintype "input"))
      (node (ref "U21") (pin "2") (pinfunction "+_2") (pintype "passive"))
      (node (ref "U21") (pin "3") (pinfunction "+_3") (pintype "passive"))
    )
    (net (code "71") (name "Net-(U19-VIN-)") (class "Default")
      (node (ref "R87") (pin "2") (pinfunction "2_2") (pintype "passive"))
      (node (ref "U19") (pin "2") (pinfunction "VIN-_2") (pintype "input"))
      (node (ref "U22") (pin "2") (pinfunction "+_2") (pintype "passive"))
      (node (ref "U22") (pin "3") (pinfunction "+_3") (pintype "passive"))
    )
    (net (code "72") (name "Net-(U20-VIN-)") (class "Default")
      (node (ref "R88") (pin "2") (pinfunction "2_2") (pintype "passive"))
      (node (ref "U20") (pin "2") (pinfunction "VIN-_2") (pintype "input"))
      (node (ref "U23") (pin "2") (pinfunction "+_2") (pintype "passive"))
      (node (ref "U23") (pin "3") (pinfunction "+_3") (pintype "passive"))
    )
    (net (code "73") (name "Net-(U21-OA)") (class "Default")
      (node (ref "C7") (pin "1") (pinfunction "1_1") (pintype "passive"))
      (node (ref "J9") (pin "1") (pinfunction "1_1") (pintype "passive"))
      (node (ref "U21") (pin "1") (pinfunction "OA_1") (pintype "passive"))
    )
    (net (code "74") (name "Net-(U21-OB)") (class "Default")
      (node (ref "C7") (pin "2") (pinfunction "2_2") (pintype "passive"))
      (node (ref "J9") (pin "2") (pinfunction "2_2") (pintype "passive"))
      (node (ref "U21") (pin "4") (pinfunction "OB_4") (pintype "passive"))
    )
    (net (code "75") (name "Net-(U22-OA)") (class "Default")
      (node (ref "C8") (pin "1") (pinfunction "1_1") (pintype "passive"))
      (node (ref "J10") (pin "1") (pinfunction "1_1") (pintype "passive"))
      (node (ref "U22") (pin "1") (pinfunction "OA_1") (pintype "passive"))
    )
    (net (code "76") (name "Net-(U22-OB)") (class "Default")
      (node (ref "C8") (pin "2") (pinfunction "2_2") (pintype "passive"))
      (node (ref "J10") (pin "2") (pinfunction "2_2") (pintype "passive"))
      (node (ref "U22") (pin "4") (pinfunction "OB_4") (pintype "passive"))
    )
    (net (code "77") (name "Net-(U23-OA)") (class "Default")
      (node (ref "C9") (pin "1") (pinfunction "1_1") (pintype "passive"))
      (node (ref "J11") (pin "1") (pinfunction "1_1") (pintype "passive"))
      (node (ref "U23") (pin "1") (pinfunction "OA_1") (pintype "passive"))
    )
    (net (code "78") (name "Net-(U23-OB)") (class "Default")
      (node (ref "C9") (pin "2") (pinfunction "2_2") (pintype "passive"))
      (node (ref "J11") (pin "2") (pinfunction "2_2") (pintype "passive"))
      (node (ref "U23") (pin "4") (pinfunction "OB_4") (pintype "passive"))
    )
    (net (code "79") (name "Net-(U24-VIN-)") (class "Default")
      (node (ref "R119") (pin "2") (pinfunction "2_2") (pintype "passive"))
      (node (ref "U24") (pin "2") (pinfunction "VIN-_2") (pintype "input"))
      (node (ref "U27") (pin "2") (pinfunction "+_2") (pintype "passive"))
      (node (ref "U27") (pin "3") (pinfunction "+_3") (pintype "passive"))
    )
    (net (code "80") (name "Net-(U25-VIN-)") (class "Default")
      (node (ref "R120") (pin "2") (pinfunction "2_2") (pintype "passive"))
      (node (ref "U25") (pin "2") (pinfunction "VIN-_2") (pintype "input"))
      (node (ref "U28") (pin "2") (pinfunction "+_2") (pintype "passive"))
      (node (ref "U28") (pin "3") (pinfunction "+_3") (pintype "passive"))
    )
    (net (code "81") (name "Net-(U26-VIN-)") (class "Default")
      (node (ref "R121") (pin "2") (pinfunction "2_2") (pintype "passive"))
      (node (ref "U26") (pin "2") (pinfunction "VIN-_2") (pintype "input"))
      (node (ref "U29") (pin "2") (pinfunction "+_2") (pintype "passive"))
      (node (ref "U29") (pin "3") (pinfunction "+_3") (pintype "passive"))
    )
    (net (code "82") (name "Net-(U27-OA)") (class "Default")
      (node (ref "C10") (pin "1") (pinfunction "1_1") (pintype "passive"))
      (node (ref "J12") (pin "1") (pinfunction "1_1") (pintype "passive"))
      (node (ref "U27") (pin "1") (pinfunction "OA_1") (pintype "passive"))
    )
    (net (code "83") (name "Net-(U27-OB)") (class "Default")
      (node (ref "C10") (pin "2") (pinfunction "2_2") (pintype "passive"))
      (node (ref "J12") (pin "2") (pinfunction "2_2") (pintype "passive"))
      (node (ref "U27") (pin "4") (pinfunction "OB_4") (pintype "passive"))
    )
    (net (code "84") (name "Net-(U28-OA)") (class "Default")
      (node (ref "C11") (pin "1") (pinfunction "1_1") (pintype "passive"))
      (node (ref "J13") (pin "1") (pinfunction "1_1") (pintype "passive"))
      (node (ref "U28") (pin "1") (pinfunction "OA_1") (pintype "passive"))
    )
    (net (code "85") (name "Net-(U28-OB)") (class "Default")
      (node (ref "C11") (pin "2") (pinfunction "2_2") (pintype "passive"))
      (node (ref "J13") (pin "2") (pinfunction "2_2") (pintype "passive"))
      (node (ref "U28") (pin "4") (pinfunction "OB_4") (pintype "passive"))
    )
    (net (code "86") (name "Net-(U29-OA)") (class "Default")
      (node (ref "C12") (pin "1") (pinfunction "1_1") (pintype "passive"))
      (node (ref "J14") (pin "1") (pinfunction "1_1") (pintype "passive"))
      (node (ref "U29") (pin "1") (pinfunction "OA_1") (pintype "passive"))
    )
    (net (code "87") (name "Net-(U29-OB)") (class "Default")
      (node (ref "C12") (pin "2") (pinfunction "2_2") (pintype "passive"))
      (node (ref "J14") (pin "2") (pinfunction "2_2") (pintype "passive"))
      (node (ref "U29") (pin "4") (pinfunction "OB_4") (pintype "passive"))
    )
    (net (code "88") (name "SCL_1") (class "Default")
      (node (ref "R100") (pin "1") (pinfunction "1_1") (pintype "passive"))
      (node (ref "R102") (pin "1") (pinfunction "1_1") (pintype "passive"))
      (node (ref "R128") (pin "1") (pinfunction "1_1") (pintype "passive"))
      (node (ref "R129") (pin "1") (pinfunction "1_1") (pintype "passive"))
      (node (ref "R130") (pin "1") (pinfunction "1_1") (pintype "passive"))
      (node (ref "R131") (pin "1") (pinfunction "1_1") (pintype "passive"))
      (node (ref "R133") (pin "1") (pinfunction "1_1") (pintype "passive"))
      (node (ref "R135") (pin "1") (pinfunction "1_1") (pintype "passive"))
      (node (ref "R29") (pin "1") (pinfunction "1_1") (pintype "passive"))
      (node (ref "R30") (pin "1") (pinfunction "1_1") (pintype "passive"))
      (node (ref "R31") (pin "1") (pinfunction "1_1") (pintype "passive"))
      (node (ref "R32") (pin "1") (pinfunction "1_1") (pintype "passive"))
      (node (ref "R34") (pin "1") (pinfunction "1_1") (pintype "passive"))
      (node (ref "R36") (pin "1") (pinfunction "1_1") (pintype "passive"))
      (node (ref "R62") (pin "1") (pinfunction "1_1") (pintype "passive"))
      (node (ref "R63") (pin "1") (pinfunction "1_1") (pintype "passive"))
      (node (ref "R64") (pin "1") (pinfunction "1_1") (pintype "passive"))
      (node (ref "R65") (pin "1") (pinfunction "1_1") (pintype "passive"))
      (node (ref "R67") (pin "1") (pinfunction "1_1") (pintype "passive"))
      (node (ref "R69") (pin "1") (pinfunction "1_1") (pintype "passive"))
      (node (ref "R95") (pin "1") (pinfunction "1_1") (pintype "passive"))
      (node (ref "R96") (pin "1") (pinfunction "1_1") (pintype "passive"))
      (node (ref "R97") (pin "1") (pinfunction "1_1") (pintype "passive"))
      (node (ref "R98") (pin "1") (pinfunction "1_1") (pintype "passive"))
      (node (ref "U12") (pin "5") (pinfunction "SCL_5") (pintype "input"))
      (node (ref "U13") (pin "5") (pinfunction "SCL_5") (pintype "input"))
      (node (ref "U14") (pin "5") (pinfunction "SCL_5") (pintype "input"))
      (node (ref "U18") (pin "5") (pinfunction "SCL_5") (pintype "input"))
      (node (ref "U19") (pin "5") (pinfunction "SCL_5") (pintype "input"))
      (node (ref "U20") (pin "5") (pinfunction "SCL_5") (pintype "input"))
      (node (ref "U24") (pin "5") (pinfunction "SCL_5") (pintype "input"))
      (node (ref "U25") (pin "5") (pinfunction "SCL_5") (pintype "input"))
      (node (ref "U26") (pin "5") (pinfunction "SCL_5") (pintype "input"))
      (node (ref "U6") (pin "5") (pinfunction "SCL_5") (pintype "input"))
      (node (ref "U7") (pin "5") (pinfunction "SCL_5") (pintype "input"))
      (node (ref "U8") (pin "5") (pinfunction "SCL_5") (pintype "input"))
    )
    (net (code "89") (name "SDA_1") (class "Default")
      (node (ref "R101") (pin "1") (pinfunction "1_1") (pintype "passive"))
      (node (ref "R103") (pin "1") (pinfunction "1_1") (pintype "passive"))
      (node (ref "R104") (pin "1") (pinfunction "1_1") (pintype "passive"))
      (node (ref "R106") (pin "1") (pinfunction "1_1") (pintype "passive"))
      (node (ref "R108") (pin "1") (pinfunction "1_1") (pintype "passive"))
      (node (ref "R132") (pin "1") (pinfunction "1_1") (pintype "passive"))
      (node (ref "R134") (pin "1") (pinfunction "1_1") (pintype "passive"))
      (node (ref "R136") (pin "1") (pinfunction "1_1") (pintype "passive"))
      (node (ref "R137") (pin "1") (pinfunction "1_1") (pintype "passive"))
      (node (ref "R139") (pin "1") (pinfunction "1_1") (pintype "passive"))
      (node (ref "R141") (pin "1") (pinfunction "1_1") (pintype "passive"))
      (node (ref "R33") (pin "1") (pinfunction "1_1") (pintype "passive"))
      (node (ref "R35") (pin "1") (pinfunction "1_1") (pintype "passive"))
      (node (ref "R37") (pin "1") (pinfunction "1_1") (pintype "passive"))
      (node (ref "R38") (pin "1") (pinfunction "1_1") (pintype "passive"))
      (node (ref "R40") (pin "1") (pinfunction "1_1") (pintype "passive"))
      (node (ref "R42") (pin "1") (pinfunction "1_1") (pintype "passive"))
      (node (ref "R66") (pin "1") (pinfunction "1_1") (pintype "passive"))
      (node (ref "R68") (pin "1") (pinfunction "1_1") (pintype "passive"))
      (node (ref "R70") (pin "1") (pinfunction "1_1") (pintype "passive"))
      (node (ref "R71") (pin "1") (pinfunction "1_1") (pintype "passive"))
      (node (ref "R73") (pin "1") (pinfunction "1_1") (pintype "passive"))
      (node (ref "R75") (pin "1") (pinfunction "1_1") (pintype "passive"))
      (node (ref "R99") (pin "1") (pinfunction "1_1") (pintype "passive"))
      (node (ref "U12") (pin "6") (pinfunction "SDA_6") (pintype "bidirectional"))
      (node (ref "U13") (pin "6") (pinfunction "SDA_6") (pintype "bidirectional"))
      (node (ref "U14") (pin "6") (pinfunction "SDA_6") (pintype "bidirectional"))
      (node (ref "U18") (pin "6") (pinfunction "SDA_6") (pintype "bidirectional"))
      (node (ref "U19") (pin "6") (pinfunction "SDA_6") (pintype "bidirectional"))
      (node (ref "U20") (pin "6") (pinfunction "SDA_6") (pintype "bidirectional"))
      (node (ref "U24") (pin "6") (pinfunction "SDA_6") (pintype "bidirectional"))
      (node (ref "U25") (pin "6") (pinfunction "SDA_6") (pintype "bidirectional"))
      (node (ref "U26") (pin "6") (pinfunction "SDA_6") (pintype "bidirectional"))
      (node (ref "U6") (pin "6") (pinfunction "SDA_6") (pintype "bidirectional"))
      (node (ref "U7") (pin "6") (pinfunction "SDA_6") (pintype "bidirectional"))
      (node (ref "U8") (pin "6") (pinfunction "SDA_6") (pintype "bidirectional"))
    )
  )
)
